# canSlaveV05.net
KiCad netlist of a schematic drawn in EAGLE
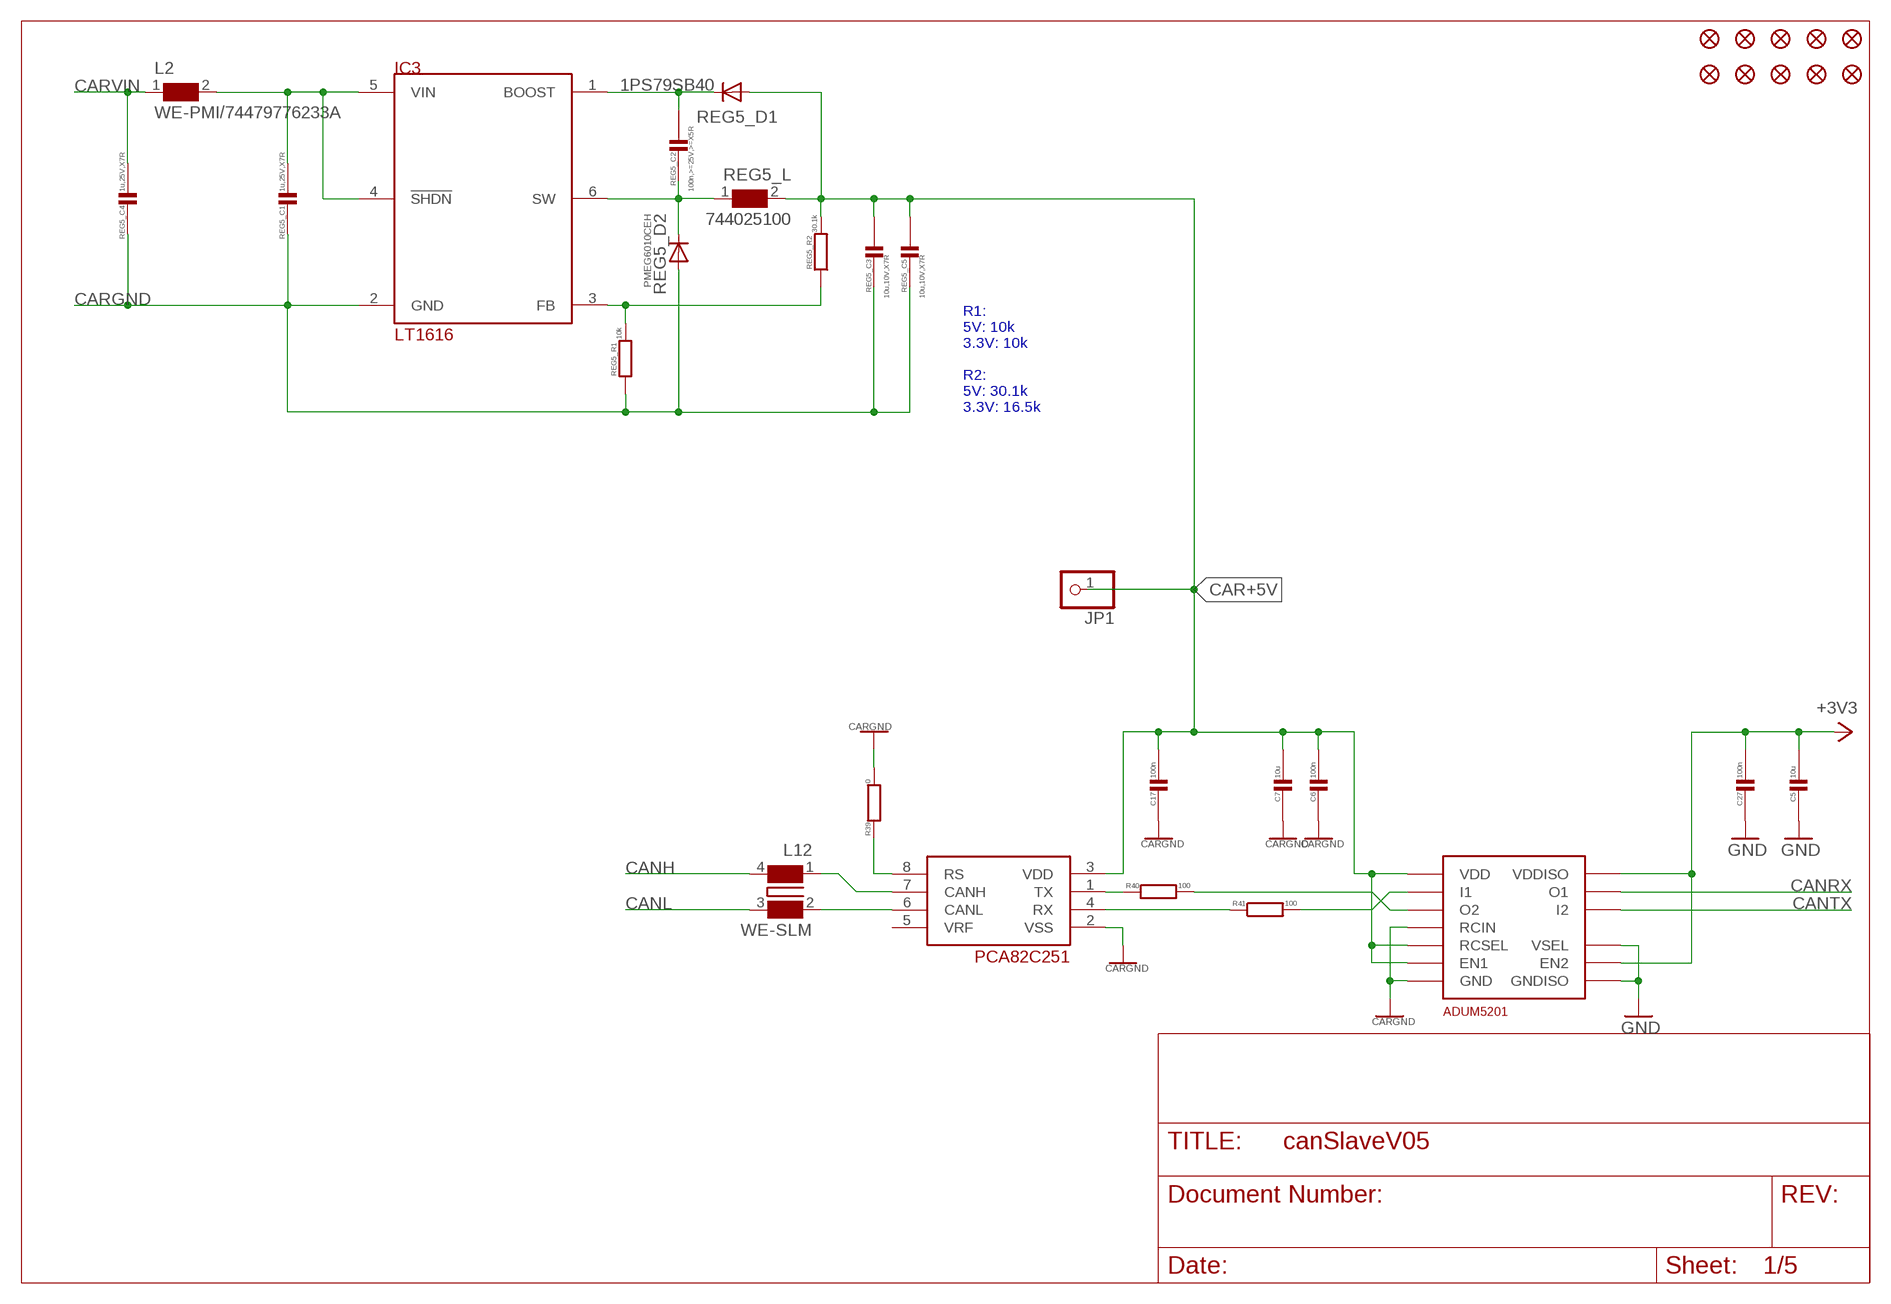
[diagram p0: schematic, sheet 1]
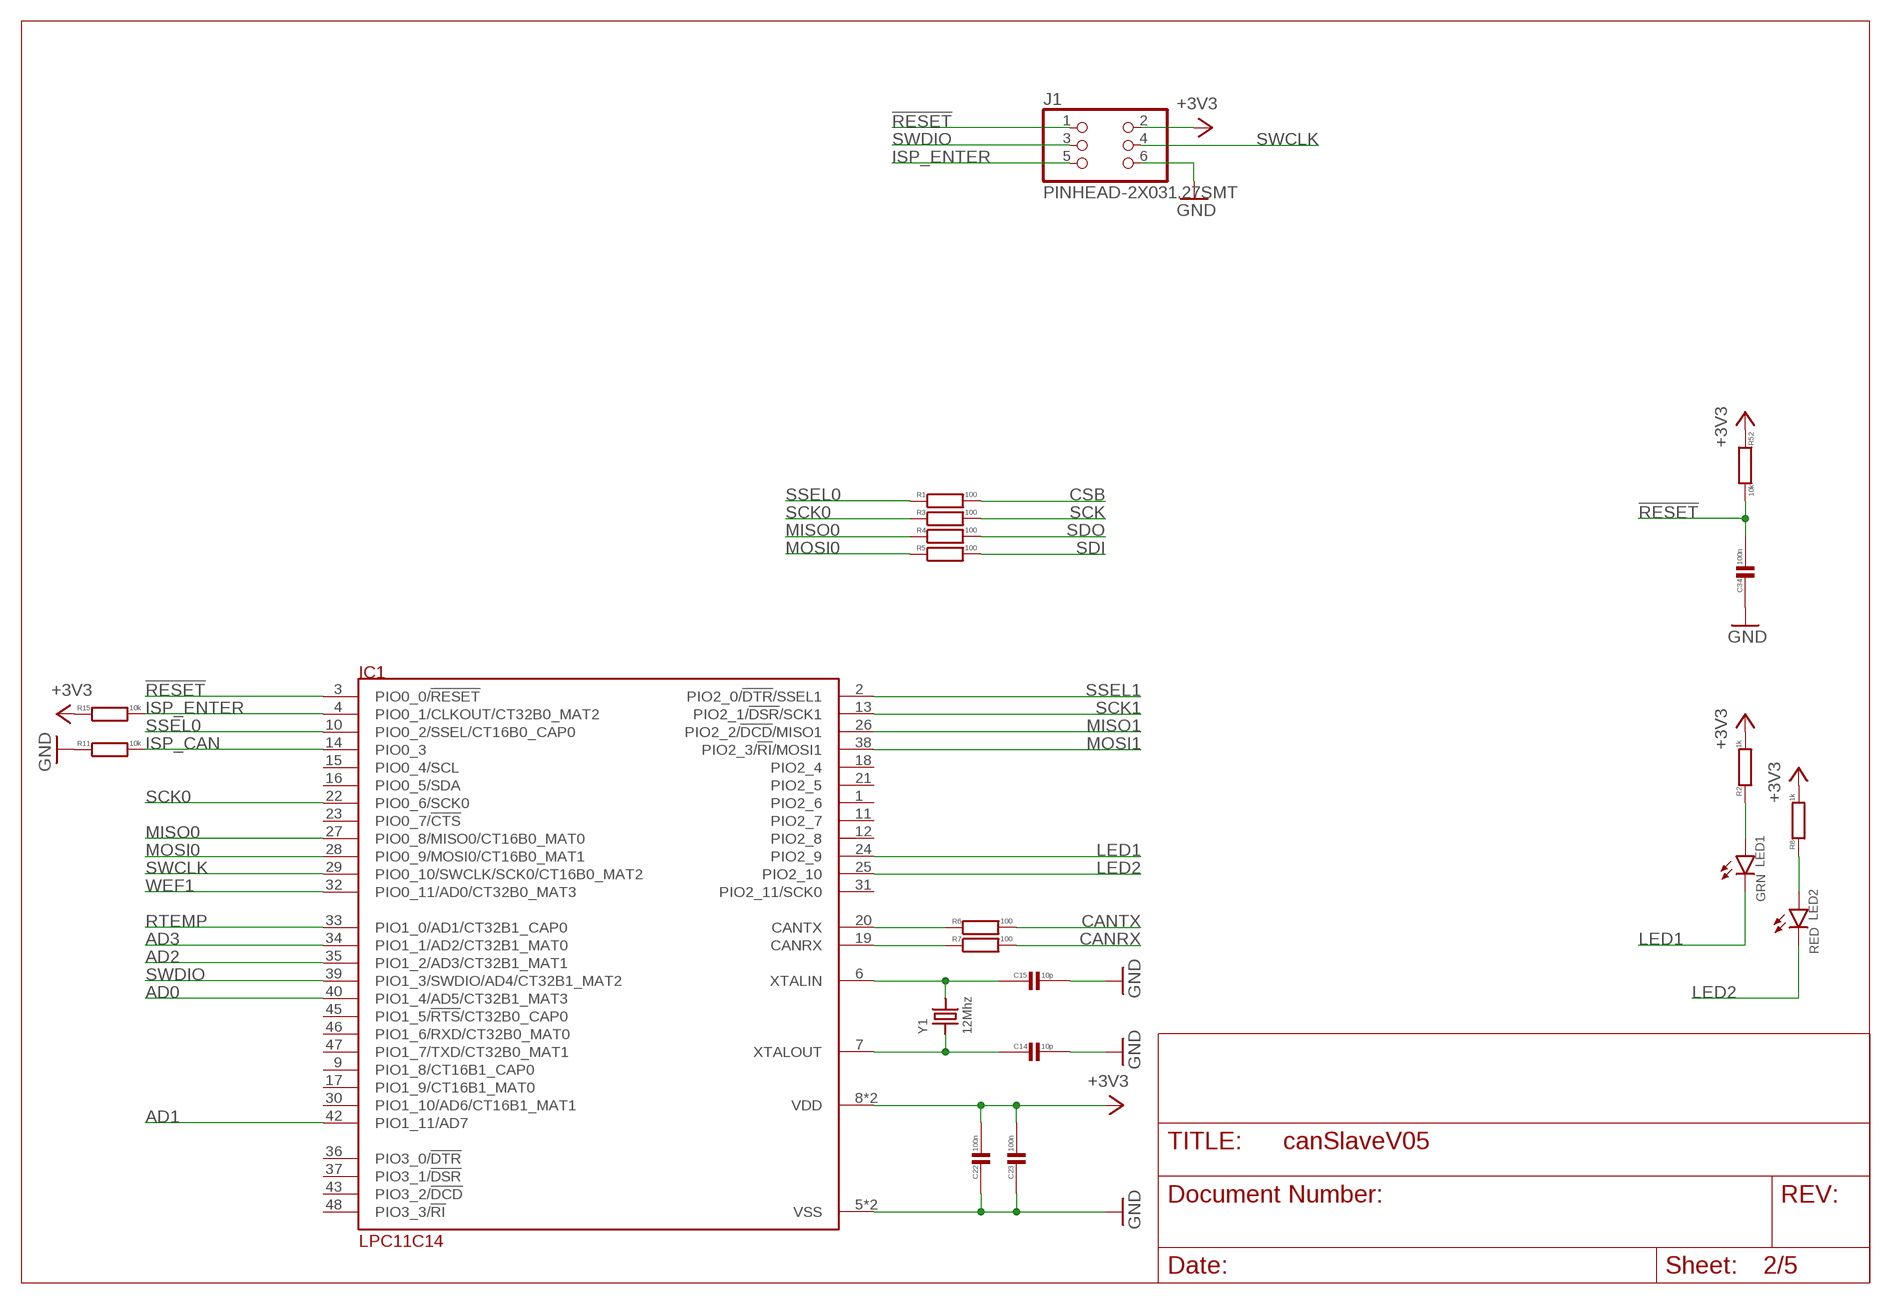
[diagram p1: schematic, sheet 2]
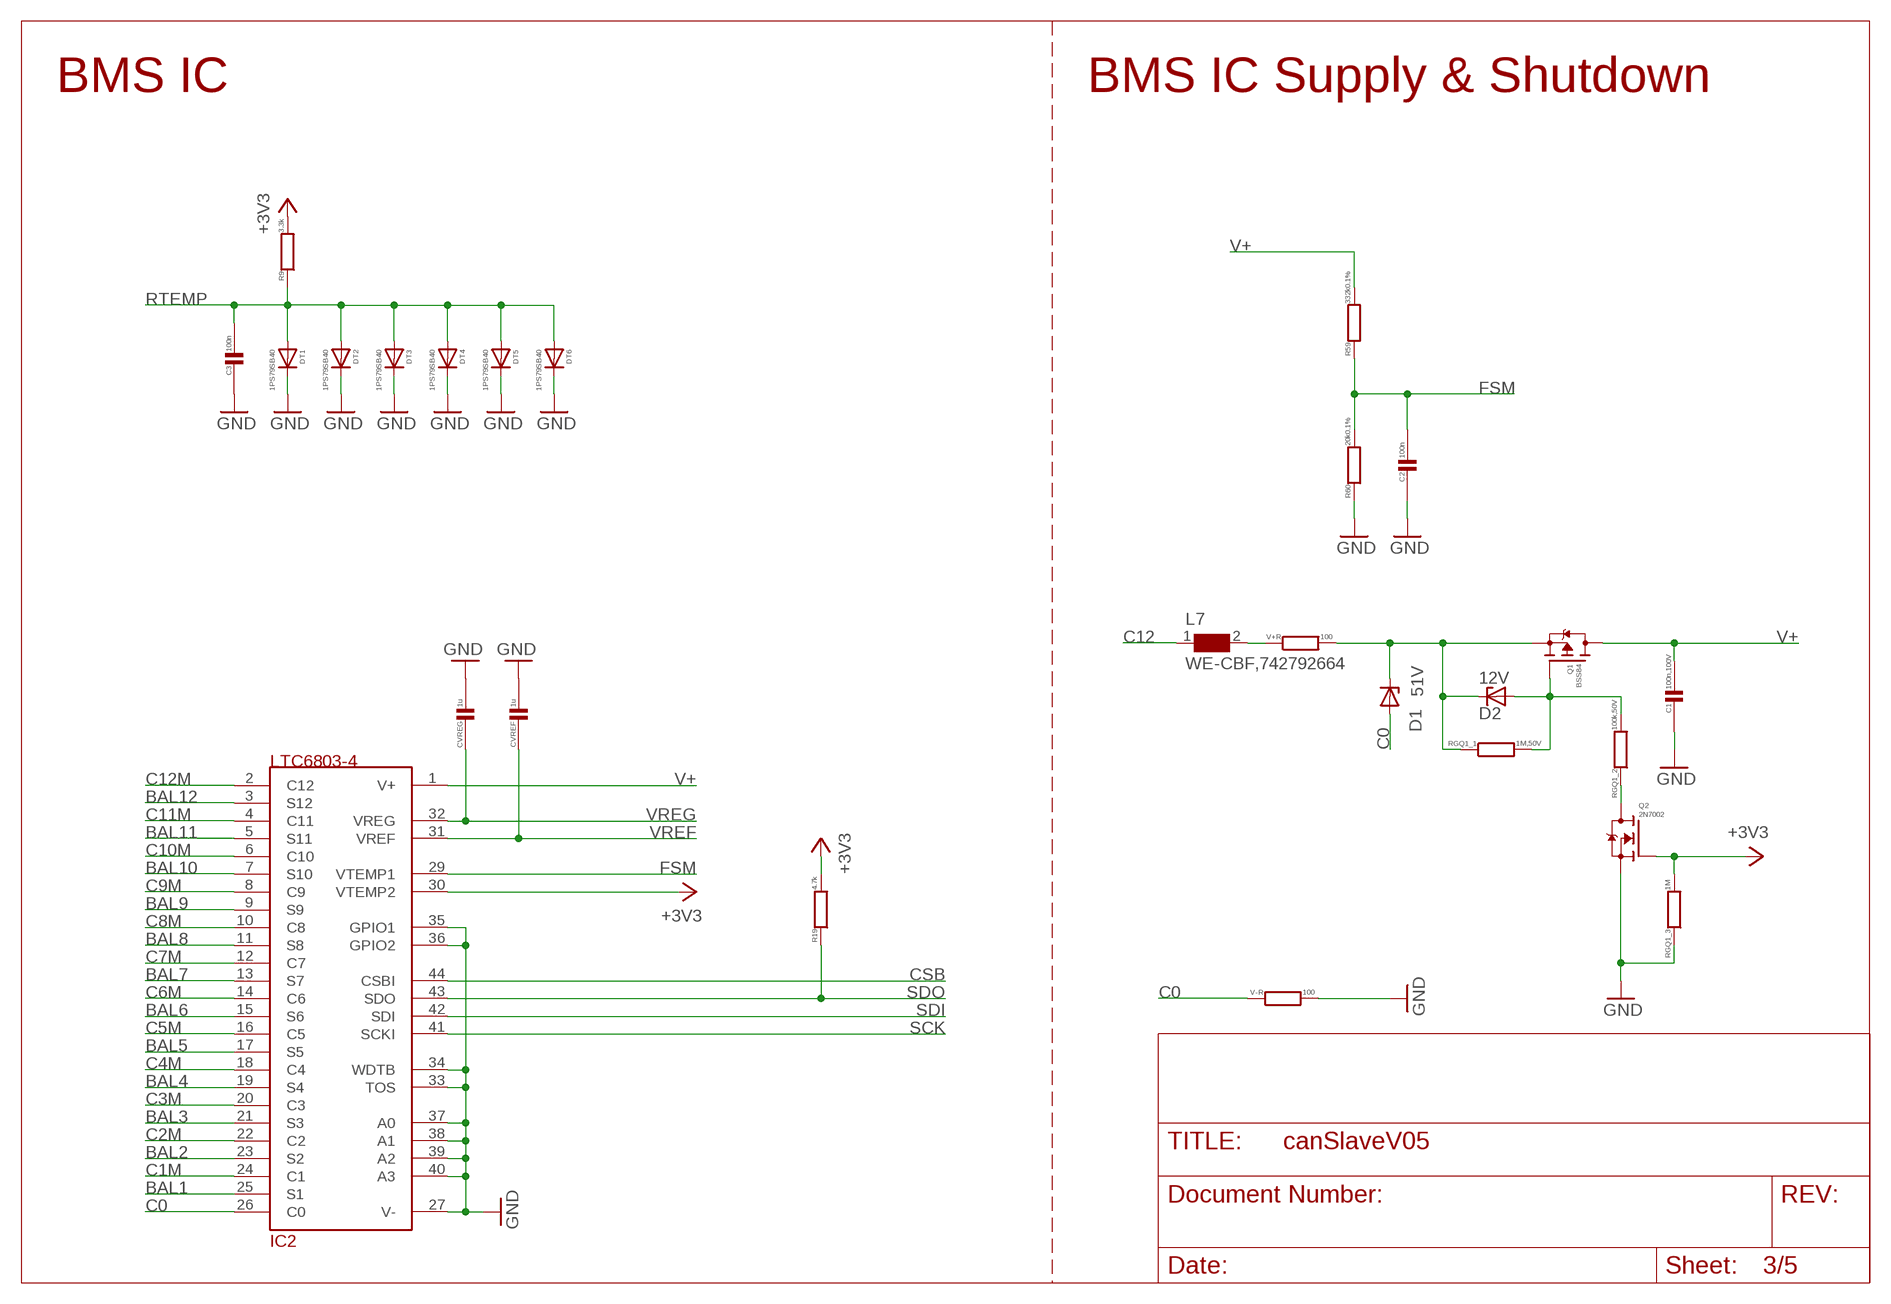
[diagram p2: schematic, sheet 3]
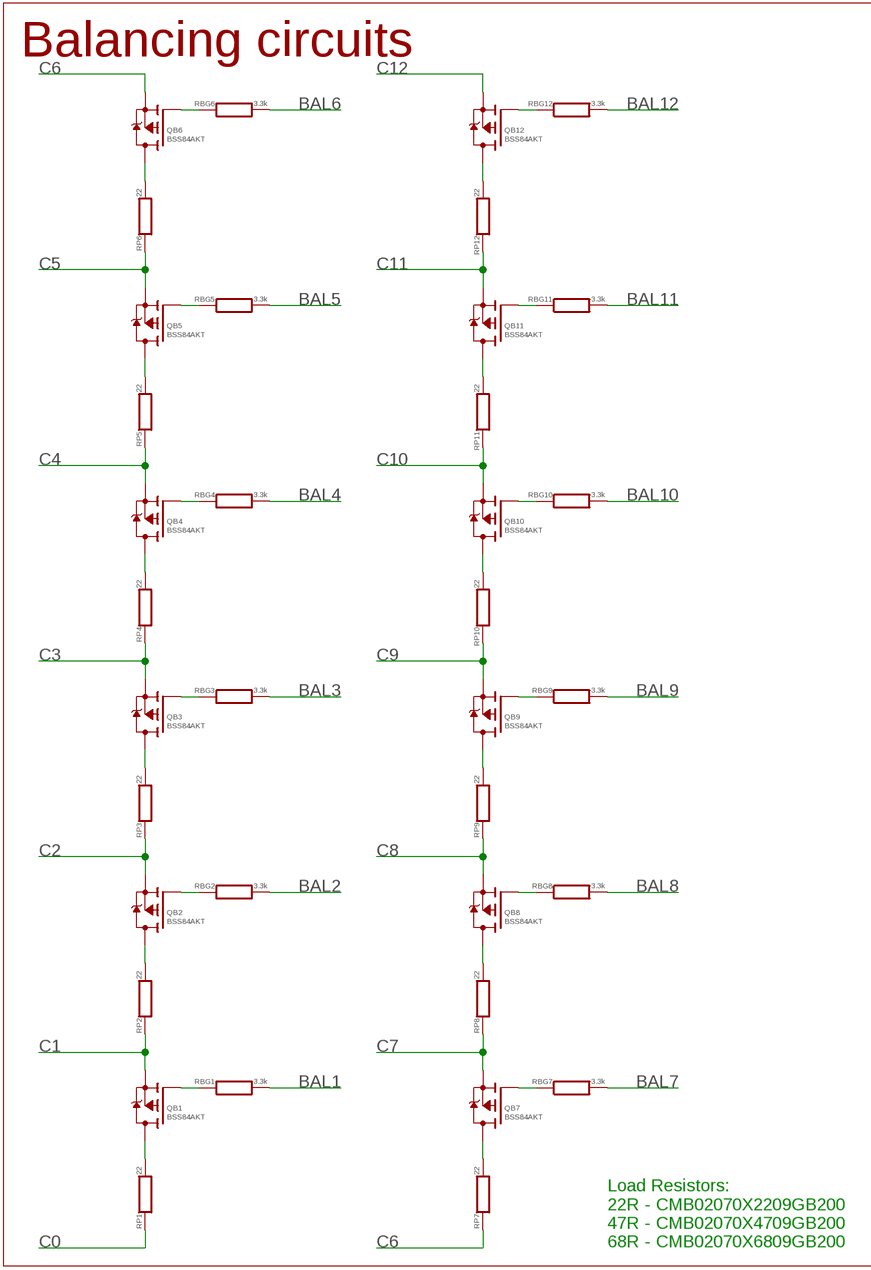
[diagram p3: schematic, sheet 4, part 1 of 2]
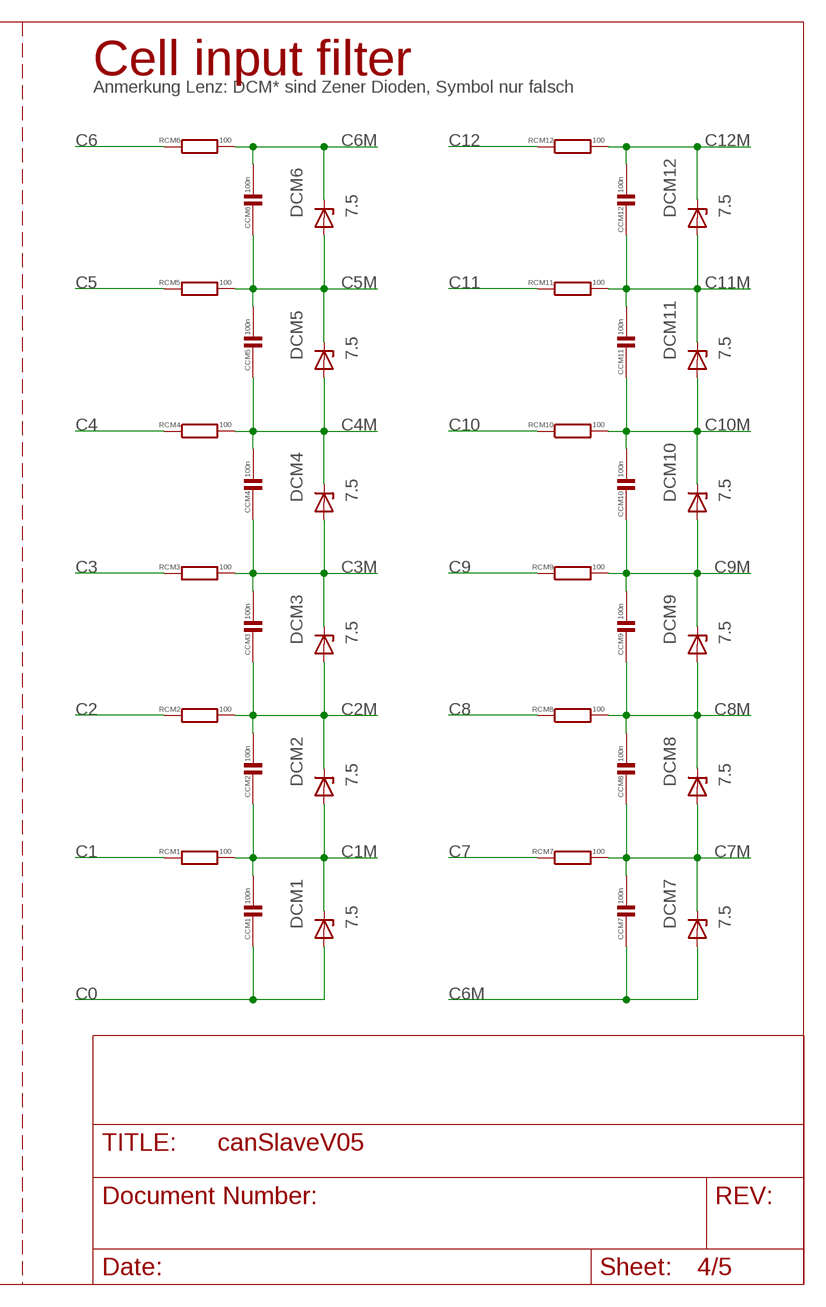
[diagram p4: schematic, sheet 4, part 2 of 2]
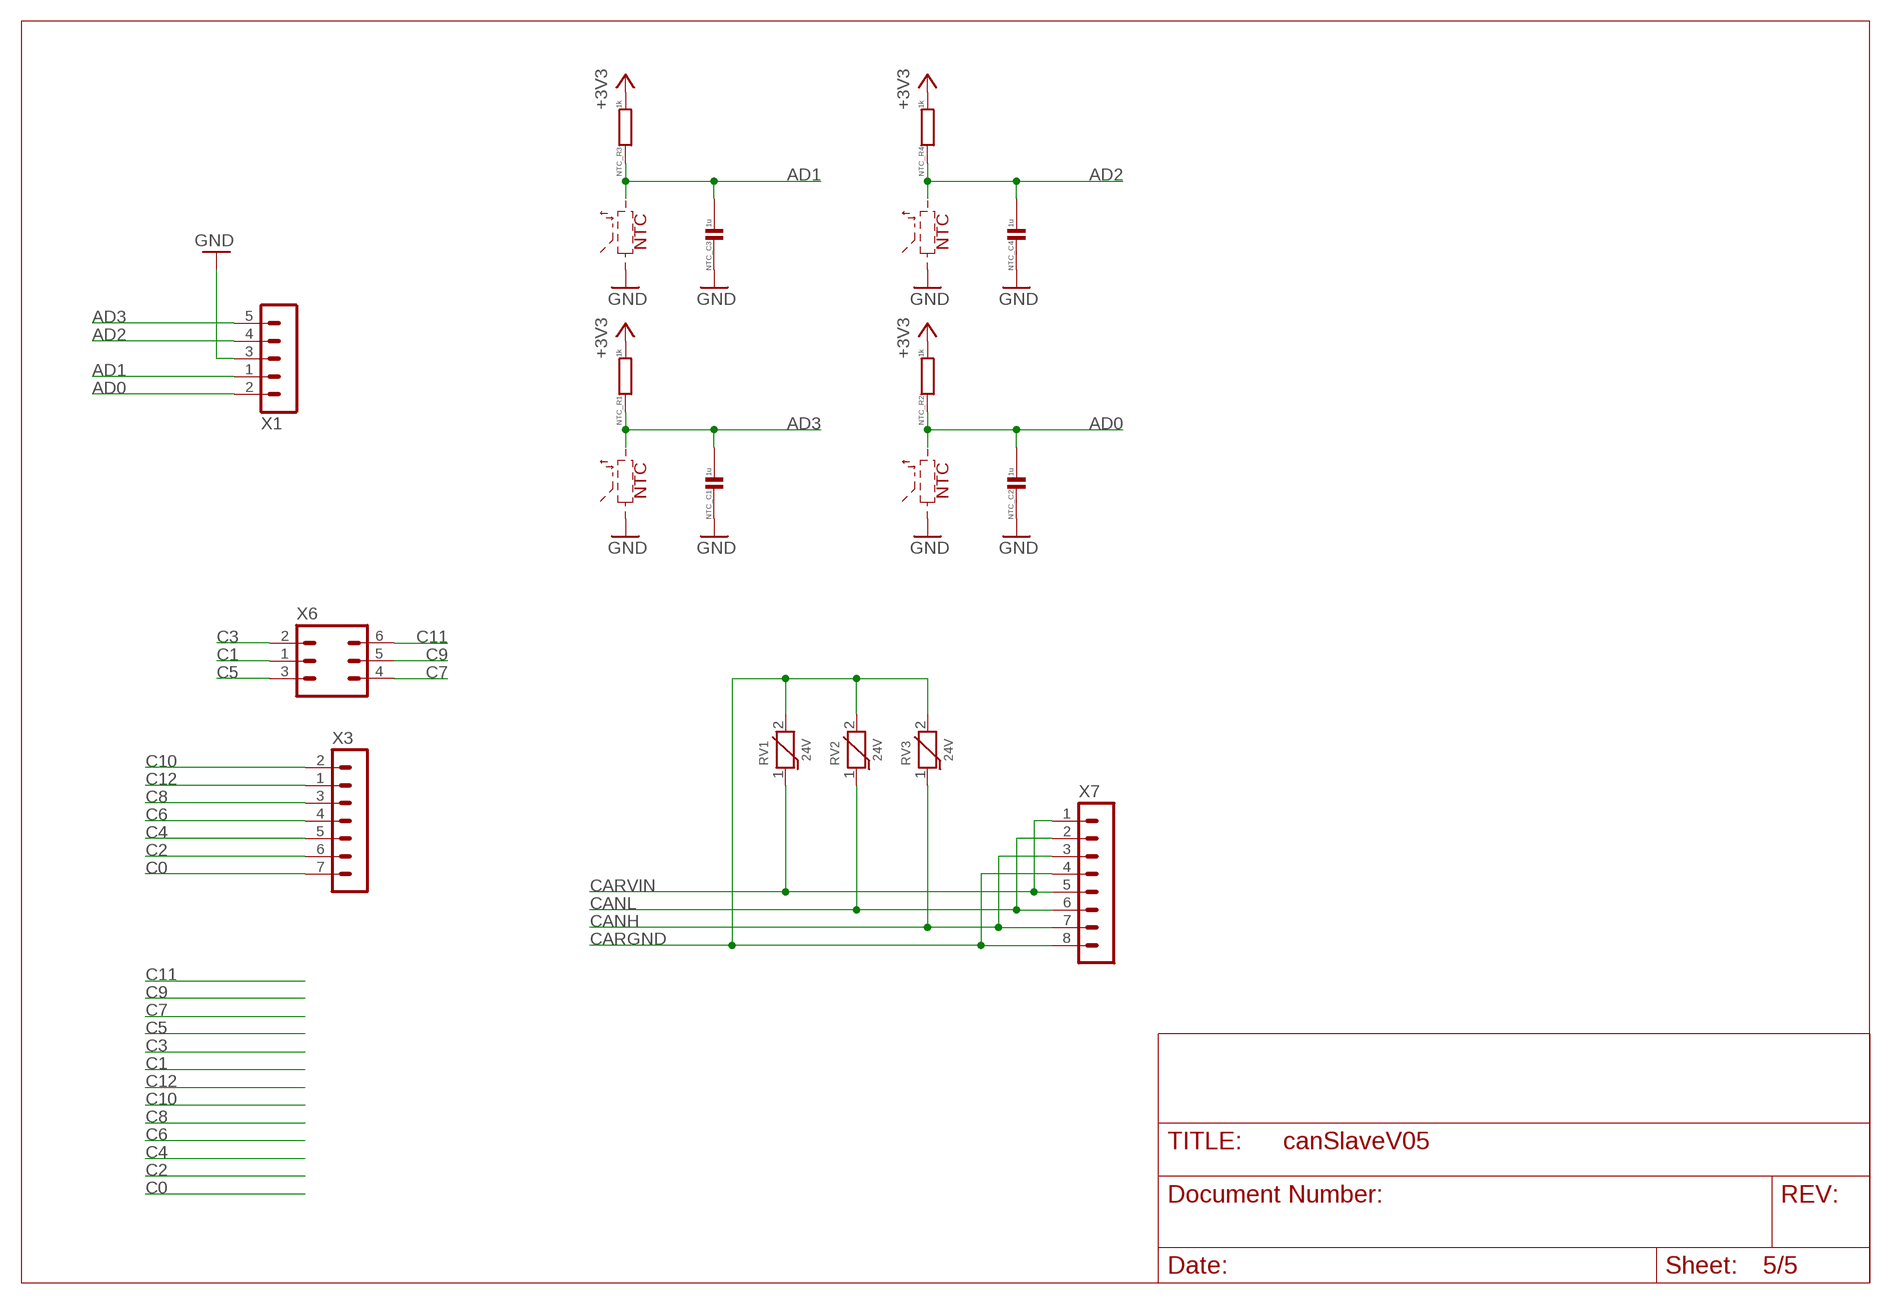
[diagram p5: schematic, sheet 5]

(export (version "E")
  (design (tool "Eeschema 10.0.6"))
  (components
    (comp (ref "CCM1")
      (value "100n")
      (footprint "eagle-import:C0402")
      (libsource (lib "eagle-import") (part "C0402"))
    )
    (comp (ref "CCM2")
      (value "100n")
      (footprint "eagle-import:C0402")
      (libsource (lib "eagle-import") (part "C0402"))
    )
    (comp (ref "CCM3")
      (value "100n")
      (footprint "eagle-import:C0402")
      (libsource (lib "eagle-import") (part "C0402"))
    )
    (comp (ref "CCM4")
      (value "100n")
      (footprint "eagle-import:C0402")
      (libsource (lib "eagle-import") (part "C0402"))
    )
    (comp (ref "CCM5")
      (value "100n")
      (footprint "eagle-import:C0402")
      (libsource (lib "eagle-import") (part "C0402"))
    )
    (comp (ref "CCM6")
      (value "100n")
      (footprint "eagle-import:C0402")
      (libsource (lib "eagle-import") (part "C0402"))
    )
    (comp (ref "CCM7")
      (value "100n")
      (footprint "eagle-import:C0402")
      (libsource (lib "eagle-import") (part "C0402"))
    )
    (comp (ref "CCM8")
      (value "100n")
      (footprint "eagle-import:C0402")
      (libsource (lib "eagle-import") (part "C0402"))
    )
    (comp (ref "CCM9")
      (value "100n")
      (footprint "eagle-import:C0402")
      (libsource (lib "eagle-import") (part "C0402"))
    )
    (comp (ref "CCM10")
      (value "100n")
      (footprint "eagle-import:C0402")
      (libsource (lib "eagle-import") (part "C0402"))
    )
    (comp (ref "CCM11")
      (value "100n")
      (footprint "eagle-import:C0402")
      (libsource (lib "eagle-import") (part "C0402"))
    )
    (comp (ref "CCM12")
      (value "100n")
      (footprint "eagle-import:C0402")
      (libsource (lib "eagle-import") (part "C0402"))
    )
    (comp (ref "DCM1")
      (value "7.5")
      (footprint "eagle-import:SOD523")
      (libsource (lib "eagle-import") (part "ZENERSOD523"))
    )
    (comp (ref "DCM2")
      (value "7.5")
      (footprint "eagle-import:SOD523")
      (libsource (lib "eagle-import") (part "ZENERSOD523"))
    )
    (comp (ref "DCM3")
      (value "7.5")
      (footprint "eagle-import:SOD523")
      (libsource (lib "eagle-import") (part "ZENERSOD523"))
    )
    (comp (ref "DCM4")
      (value "7.5")
      (footprint "eagle-import:SOD523")
      (libsource (lib "eagle-import") (part "ZENERSOD523"))
    )
    (comp (ref "DCM5")
      (value "7.5")
      (footprint "eagle-import:SOD523")
      (libsource (lib "eagle-import") (part "ZENERSOD523"))
    )
    (comp (ref "DCM6")
      (value "7.5")
      (footprint "eagle-import:SOD523")
      (libsource (lib "eagle-import") (part "ZENERSOD523"))
    )
    (comp (ref "DCM7")
      (value "7.5")
      (footprint "eagle-import:SOD523")
      (libsource (lib "eagle-import") (part "ZENERSOD523"))
    )
    (comp (ref "DCM8")
      (value "7.5")
      (footprint "eagle-import:SOD523")
      (libsource (lib "eagle-import") (part "ZENERSOD523"))
    )
    (comp (ref "DCM9")
      (value "7.5")
      (footprint "eagle-import:SOD523")
      (libsource (lib "eagle-import") (part "ZENERSOD523"))
    )
    (comp (ref "DCM10")
      (value "7.5")
      (footprint "eagle-import:SOD523")
      (libsource (lib "eagle-import") (part "ZENERSOD523"))
    )
    (comp (ref "DCM11")
      (value "7.5")
      (footprint "eagle-import:SOD523")
      (libsource (lib "eagle-import") (part "ZENERSOD523"))
    )
    (comp (ref "DCM12")
      (value "7.5")
      (footprint "eagle-import:SOD523")
      (libsource (lib "eagle-import") (part "ZENERSOD523"))
    )
    (comp (ref "QB1")
      (value "BSS84AKT")
      (footprint "eagle-import:SOT416")
      (libsource (lib "eagle-import") (part "BSS84AKT"))
    )
    (comp (ref "QB2")
      (value "BSS84AKT")
      (footprint "eagle-import:SOT416")
      (libsource (lib "eagle-import") (part "BSS84AKT"))
    )
    (comp (ref "QB3")
      (value "BSS84AKT")
      (footprint "eagle-import:SOT416")
      (libsource (lib "eagle-import") (part "BSS84AKT"))
    )
    (comp (ref "QB4")
      (value "BSS84AKT")
      (footprint "eagle-import:SOT416")
      (libsource (lib "eagle-import") (part "BSS84AKT"))
    )
    (comp (ref "QB5")
      (value "BSS84AKT")
      (footprint "eagle-import:SOT416")
      (libsource (lib "eagle-import") (part "BSS84AKT"))
    )
    (comp (ref "QB6")
      (value "BSS84AKT")
      (footprint "eagle-import:SOT416")
      (libsource (lib "eagle-import") (part "BSS84AKT"))
    )
    (comp (ref "QB7")
      (value "BSS84AKT")
      (footprint "eagle-import:SOT416")
      (libsource (lib "eagle-import") (part "BSS84AKT"))
    )
    (comp (ref "QB8")
      (value "BSS84AKT")
      (footprint "eagle-import:SOT416")
      (libsource (lib "eagle-import") (part "BSS84AKT"))
    )
    (comp (ref "QB9")
      (value "BSS84AKT")
      (footprint "eagle-import:SOT416")
      (libsource (lib "eagle-import") (part "BSS84AKT"))
    )
    (comp (ref "QB10")
      (value "BSS84AKT")
      (footprint "eagle-import:SOT416")
      (libsource (lib "eagle-import") (part "BSS84AKT"))
    )
    (comp (ref "QB11")
      (value "BSS84AKT")
      (footprint "eagle-import:SOT416")
      (libsource (lib "eagle-import") (part "BSS84AKT"))
    )
    (comp (ref "QB12")
      (value "BSS84AKT")
      (footprint "eagle-import:SOT416")
      (libsource (lib "eagle-import") (part "BSS84AKT"))
    )
    (comp (ref "RBG1")
      (value "3.3k")
      (footprint "eagle-import:R0402")
      (libsource (lib "eagle-import") (part "R0402"))
    )
    (comp (ref "RBG2")
      (value "3.3k")
      (footprint "eagle-import:R0402")
      (libsource (lib "eagle-import") (part "R0402"))
    )
    (comp (ref "RBG3")
      (value "3.3k")
      (footprint "eagle-import:R0402")
      (libsource (lib "eagle-import") (part "R0402"))
    )
    (comp (ref "RBG4")
      (value "3.3k")
      (footprint "eagle-import:R0402")
      (libsource (lib "eagle-import") (part "R0402"))
    )
    (comp (ref "RBG5")
      (value "3.3k")
      (footprint "eagle-import:R0402")
      (libsource (lib "eagle-import") (part "R0402"))
    )
    (comp (ref "RBG6")
      (value "3.3k")
      (footprint "eagle-import:R0402")
      (libsource (lib "eagle-import") (part "R0402"))
    )
    (comp (ref "RBG7")
      (value "3.3k")
      (footprint "eagle-import:R0402")
      (libsource (lib "eagle-import") (part "R0402"))
    )
    (comp (ref "RBG8")
      (value "3.3k")
      (footprint "eagle-import:R0402")
      (libsource (lib "eagle-import") (part "R0402"))
    )
    (comp (ref "RBG9")
      (value "3.3k")
      (footprint "eagle-import:R0402")
      (libsource (lib "eagle-import") (part "R0402"))
    )
    (comp (ref "RBG10")
      (value "3.3k")
      (footprint "eagle-import:R0402")
      (libsource (lib "eagle-import") (part "R0402"))
    )
    (comp (ref "RBG11")
      (value "3.3k")
      (footprint "eagle-import:R0402")
      (libsource (lib "eagle-import") (part "R0402"))
    )
    (comp (ref "RBG12")
      (value "3.3k")
      (footprint "eagle-import:R0402")
      (libsource (lib "eagle-import") (part "R0402"))
    )
    (comp (ref "RCM1")
      (value "100")
      (footprint "eagle-import:R0402")
      (libsource (lib "eagle-import") (part "R0402"))
    )
    (comp (ref "RCM2")
      (value "100")
      (footprint "eagle-import:R0402")
      (libsource (lib "eagle-import") (part "R0402"))
    )
    (comp (ref "RCM3")
      (value "100")
      (footprint "eagle-import:R0402")
      (libsource (lib "eagle-import") (part "R0402"))
    )
    (comp (ref "RCM4")
      (value "100")
      (footprint "eagle-import:R0402")
      (libsource (lib "eagle-import") (part "R0402"))
    )
    (comp (ref "RCM5")
      (value "100")
      (footprint "eagle-import:R0402")
      (libsource (lib "eagle-import") (part "R0402"))
    )
    (comp (ref "RCM6")
      (value "100")
      (footprint "eagle-import:R0402")
      (libsource (lib "eagle-import") (part "R0402"))
    )
    (comp (ref "RCM7")
      (value "100")
      (footprint "eagle-import:R0402")
      (libsource (lib "eagle-import") (part "R0402"))
    )
    (comp (ref "RCM8")
      (value "100")
      (footprint "eagle-import:R0402")
      (libsource (lib "eagle-import") (part "R0402"))
    )
    (comp (ref "RCM9")
      (value "100")
      (footprint "eagle-import:R0402")
      (libsource (lib "eagle-import") (part "R0402"))
    )
    (comp (ref "RCM10")
      (value "100")
      (footprint "eagle-import:R0402")
      (libsource (lib "eagle-import") (part "R0402"))
    )
    (comp (ref "RCM11")
      (value "100")
      (footprint "eagle-import:R0402")
      (libsource (lib "eagle-import") (part "R0402"))
    )
    (comp (ref "RCM12")
      (value "100")
      (footprint "eagle-import:R0402")
      (libsource (lib "eagle-import") (part "R0402"))
    )
    (comp (ref "RP1")
      (value "22")
      (footprint "eagle-import:MINI_MELF-0207R")
      (libsource (lib "eagle-import") (part "RMELF-0207R"))
    )
    (comp (ref "RP2")
      (value "22")
      (footprint "eagle-import:MINI_MELF-0207R")
      (libsource (lib "eagle-import") (part "RMELF-0207R"))
    )
    (comp (ref "RP3")
      (value "22")
      (footprint "eagle-import:MINI_MELF-0207R")
      (libsource (lib "eagle-import") (part "RMELF-0207R"))
    )
    (comp (ref "RP4")
      (value "22")
      (footprint "eagle-import:MINI_MELF-0207R")
      (libsource (lib "eagle-import") (part "RMELF-0207R"))
    )
    (comp (ref "RP5")
      (value "22")
      (footprint "eagle-import:MINI_MELF-0207R")
      (libsource (lib "eagle-import") (part "RMELF-0207R"))
    )
    (comp (ref "RP6")
      (value "22")
      (footprint "eagle-import:MINI_MELF-0207R")
      (libsource (lib "eagle-import") (part "RMELF-0207R"))
    )
    (comp (ref "RP7")
      (value "22")
      (footprint "eagle-import:MINI_MELF-0207R")
      (libsource (lib "eagle-import") (part "RMELF-0207R"))
    )
    (comp (ref "RP8")
      (value "22")
      (footprint "eagle-import:MINI_MELF-0207R")
      (libsource (lib "eagle-import") (part "RMELF-0207R"))
    )
    (comp (ref "RP9")
      (value "22")
      (footprint "eagle-import:MINI_MELF-0207R")
      (libsource (lib "eagle-import") (part "RMELF-0207R"))
    )
    (comp (ref "RP10")
      (value "22")
      (footprint "eagle-import:MINI_MELF-0207R")
      (libsource (lib "eagle-import") (part "RMELF-0207R"))
    )
    (comp (ref "RP11")
      (value "22")
      (footprint "eagle-import:MINI_MELF-0207R")
      (libsource (lib "eagle-import") (part "RMELF-0207R"))
    )
    (comp (ref "RP12")
      (value "22")
      (footprint "eagle-import:MINI_MELF-0207R")
      (libsource (lib "eagle-import") (part "RMELF-0207R"))
    )
    (comp (ref "C1")
      (value "100n,100V")
      (footprint "eagle-import:C0603")
      (libsource (lib "eagle-import") (part "C0603"))
    )
    (comp (ref "C2")
      (value "100n")
      (footprint "eagle-import:C0402")
      (libsource (lib "eagle-import") (part "C0402"))
    )
    (comp (ref "C3")
      (value "100n")
      (footprint "eagle-import:C0402")
      (libsource (lib "eagle-import") (part "C0402"))
    )
    (comp (ref "CVREF")
      (value "1u")
      (footprint "eagle-import:C0402")
      (libsource (lib "eagle-import") (part "C0402"))
    )
    (comp (ref "CVREG")
      (value "1u")
      (footprint "eagle-import:C0402")
      (libsource (lib "eagle-import") (part "C0402"))
    )
    (comp (ref "D1")
      (value "51V")
      (footprint "eagle-import:SOD323-L")
      (libsource (lib "eagle-import") (part "ZENERSOD323"))
    )
    (comp (ref "D2")
      (value "12V")
      (footprint "eagle-import:SOD323-L")
      (libsource (lib "eagle-import") (part "ZENERSOD323"))
    )
    (comp (ref "DT1")
      (value "1PS79SB40")
      (footprint "eagle-import:SOD523")
      (libsource (lib "eagle-import") (part "DIODE-SOD523"))
    )
    (comp (ref "DT2")
      (value "1PS79SB40")
      (footprint "eagle-import:SOD523")
      (libsource (lib "eagle-import") (part "DIODE-SOD523"))
    )
    (comp (ref "DT3")
      (value "1PS79SB40")
      (footprint "eagle-import:SOD523")
      (libsource (lib "eagle-import") (part "DIODE-SOD523"))
    )
    (comp (ref "DT4")
      (value "1PS79SB40")
      (footprint "eagle-import:SOD523")
      (libsource (lib "eagle-import") (part "DIODE-SOD523"))
    )
    (comp (ref "DT5")
      (value "1PS79SB40")
      (footprint "eagle-import:SOD523")
      (libsource (lib "eagle-import") (part "DIODE-SOD523"))
    )
    (comp (ref "DT6")
      (value "1PS79SB40")
      (footprint "eagle-import:SOD523")
      (libsource (lib "eagle-import") (part "DIODE-SOD523"))
    )
    (comp (ref "IC2")
      (value "LTC6803-4")
      (footprint "eagle-import:44SSOP")
      (libsource (lib "eagle-import") (part "LTC6803-4"))
    )
    (comp (ref "L7")
      (value "WE-CBF,742792664")
      (footprint "eagle-import:0603")
      (libsource (lib "eagle-import") (part "WE-CBF_0603"))
    )
    (comp (ref "Q1")
      (value "BSS84")
      (footprint "eagle-import:SOT23")
      (libsource (lib "eagle-import") (part "BSS84"))
    )
    (comp (ref "Q2")
      (value "2N7002")
      (footprint "eagle-import:SOT23")
      (libsource (lib "eagle-import") (part "2N7002"))
    )
    (comp (ref "R9")
      (value "3.3k")
      (footprint "eagle-import:R0603")
      (libsource (lib "eagle-import") (part "R0603"))
    )
    (comp (ref "R19")
      (value "4.7k")
      (footprint "eagle-import:R0402")
      (libsource (lib "eagle-import") (part "R0402"))
    )
    (comp (ref "R59")
      (value "332k0.1%")
      (footprint "eagle-import:R0603")
      (libsource (lib "eagle-import") (part "R0603"))
    )
    (comp (ref "R60")
      (value "20k0.1%")
      (footprint "eagle-import:R0402")
      (libsource (lib "eagle-import") (part "R0402"))
    )
    (comp (ref "RGQ1_1")
      (value "1M,50V")
      (footprint "eagle-import:R0603")
      (libsource (lib "eagle-import") (part "R0603"))
    )
    (comp (ref "RGQ1_2")
      (value "100k,50V")
      (footprint "eagle-import:R0603")
      (libsource (lib "eagle-import") (part "R0603"))
    )
    (comp (ref "RGQ1_3")
      (value "1M")
      (footprint "eagle-import:R0402")
      (libsource (lib "eagle-import") (part "R0402"))
    )
    (comp (ref "V+R")
      (value "100")
      (footprint "eagle-import:R0603")
      (libsource (lib "eagle-import") (part "R0603"))
    )
    (comp (ref "V-R")
      (value "100")
      (footprint "eagle-import:R0603")
      (libsource (lib "eagle-import") (part "R0603"))
    )
    (comp (ref "C14")
      (value "10p")
      (footprint "eagle-import:C0402")
      (libsource (lib "eagle-import") (part "C0402"))
    )
    (comp (ref "C15")
      (value "10p")
      (footprint "eagle-import:C0402")
      (libsource (lib "eagle-import") (part "C0402"))
    )
    (comp (ref "C22")
      (value "100n")
      (footprint "eagle-import:C0402")
      (libsource (lib "eagle-import") (part "C0402"))
    )
    (comp (ref "C23")
      (value "100n")
      (footprint "eagle-import:C0402")
      (libsource (lib "eagle-import") (part "C0402"))
    )
    (comp (ref "C34")
      (value "100n")
      (footprint "eagle-import:C0402")
      (libsource (lib "eagle-import") (part "C0402"))
    )
    (comp (ref "IC1")
      (value "LPC11C14")
      (footprint "eagle-import:LQFP48")
      (libsource (lib "eagle-import") (part "LPC11C1X"))
    )
    (comp (ref "J1")
      (value "PINHEAD-2X031.27SMT")
      (footprint "eagle-import:2X03_1.27MM_SMT")
      (libsource (lib "eagle-import") (part "PINHEAD-2X031.27SMT"))
    )
    (comp (ref "LED1")
      (value "GRN")
      (footprint "eagle-import:CHIPLED_0402")
      (libsource (lib "eagle-import") (part "LED0402"))
    )
    (comp (ref "LED2")
      (value "RED")
      (footprint "eagle-import:CHIPLED_0402")
      (libsource (lib "eagle-import") (part "LED0402"))
    )
    (comp (ref "R1")
      (value "100")
      (footprint "eagle-import:R0402")
      (libsource (lib "eagle-import") (part "R0402"))
    )
    (comp (ref "R2")
      (value "1k")
      (footprint "eagle-import:R0402")
      (libsource (lib "eagle-import") (part "R0402"))
    )
    (comp (ref "R3")
      (value "100")
      (footprint "eagle-import:R0402")
      (libsource (lib "eagle-import") (part "R0402"))
    )
    (comp (ref "R4")
      (value "100")
      (footprint "eagle-import:R0402")
      (libsource (lib "eagle-import") (part "R0402"))
    )
    (comp (ref "R5")
      (value "100")
      (footprint "eagle-import:R0402")
      (libsource (lib "eagle-import") (part "R0402"))
    )
    (comp (ref "R6")
      (value "100")
      (footprint "eagle-import:R0402")
      (libsource (lib "eagle-import") (part "R0402"))
    )
    (comp (ref "R7")
      (value "100")
      (footprint "eagle-import:R0402")
      (libsource (lib "eagle-import") (part "R0402"))
    )
    (comp (ref "R8")
      (value "1k")
      (footprint "eagle-import:R0402")
      (libsource (lib "eagle-import") (part "R0402"))
    )
    (comp (ref "R11")
      (value "10k")
      (footprint "eagle-import:R0402")
      (libsource (lib "eagle-import") (part "R0402"))
    )
    (comp (ref "R15")
      (value "10k")
      (footprint "eagle-import:R0402")
      (libsource (lib "eagle-import") (part "R0402"))
    )
    (comp (ref "R52")
      (value "10k")
      (footprint "eagle-import:R0402")
      (libsource (lib "eagle-import") (part "R0402"))
    )
    (comp (ref "Y1")
      (value "12Mhz")
      (footprint "eagle-import:CRYSTAL_3.2X2.5")
      (libsource (lib "eagle-import") (part "CRYSTALTHIN"))
    )
    (comp (ref "NTC_C1")
      (value "1u")
      (footprint "eagle-import:C0402")
      (libsource (lib "eagle-import") (part "C0402"))
    )
    (comp (ref "NTC_C2")
      (value "1u")
      (footprint "eagle-import:C0402")
      (libsource (lib "eagle-import") (part "C0402"))
    )
    (comp (ref "NTC_C3")
      (value "1u")
      (footprint "eagle-import:C0402")
      (libsource (lib "eagle-import") (part "C0402"))
    )
    (comp (ref "NTC_C4")
      (value "1u")
      (footprint "eagle-import:C0402")
      (libsource (lib "eagle-import") (part "C0402"))
    )
    (comp (ref "NTC_R1")
      (value "1k")
      (footprint "eagle-import:R0402")
      (libsource (lib "eagle-import") (part "R0402"))
    )
    (comp (ref "NTC_R2")
      (value "1k")
      (footprint "eagle-import:R0402")
      (libsource (lib "eagle-import") (part "R0402"))
    )
    (comp (ref "NTC_R3")
      (value "1k")
      (footprint "eagle-import:R0402")
      (libsource (lib "eagle-import") (part "R0402"))
    )
    (comp (ref "NTC_R4")
      (value "1k")
      (footprint "eagle-import:R0402")
      (libsource (lib "eagle-import") (part "R0402"))
    )
    (comp (ref "RV1")
      (value "24V")
      (footprint "eagle-import:R0805")
      (libsource (lib "eagle-import") (part "VARISTOR0805"))
    )
    (comp (ref "RV2")
      (value "24V")
      (footprint "eagle-import:R0603")
      (libsource (lib "eagle-import") (part "VARISTOR0603"))
    )
    (comp (ref "RV3")
      (value "24V")
      (footprint "eagle-import:R0603")
      (libsource (lib "eagle-import") (part "VARISTOR0603"))
    )
    (comp (ref "X1")
      (value "HEADER_POS5_43650-0509")
      (footprint "eagle-import:43650-0509")
      (libsource (lib "eagle-import") (part "HEADER_POS5_?43650-0509"))
    )
    (comp (ref "X3")
      (value "HEADER_POS7_43650-0709")
      (footprint "eagle-import:43650-0709")
      (libsource (lib "eagle-import") (part "HEADER_POS7_?43650-0709"))
    )
    (comp (ref "X6")
      (value "HEADER_POS6_43650-0609")
      (footprint "eagle-import:43650-0609")
      (libsource (lib "eagle-import") (part "HEADER_POS6_?43650-0609"))
    )
    (comp (ref "X7")
      (value "HEADER_POS8_43045-0800")
      (footprint "eagle-import:43045-0800")
      (libsource (lib "eagle-import") (part "HEADER_POS8_?43045-0800"))
    )
    (comp (ref "C5")
      (value "10u")
      (footprint "eagle-import:C0603")
      (libsource (lib "eagle-import") (part "C0603"))
    )
    (comp (ref "C6")
      (value "100n")
      (footprint "eagle-import:C0402")
      (libsource (lib "eagle-import") (part "C0402"))
    )
    (comp (ref "C7")
      (value "10u")
      (footprint "eagle-import:C0603")
      (libsource (lib "eagle-import") (part "C0603"))
    )
    (comp (ref "C17")
      (value "100n")
      (footprint "eagle-import:C0402")
      (libsource (lib "eagle-import") (part "C0402"))
    )
    (comp (ref "C27")
      (value "100n")
      (footprint "eagle-import:C0402")
      (libsource (lib "eagle-import") (part "C0402"))
    )
    (comp (ref "FID1")
      (value "FIDUCIAL\"\"")
      (footprint "eagle-import:FIDUCIAL_1MM")
      (libsource (lib "eagle-import") (part "FIDUCIAL{dblquote}{dblquote}"))
    )
    (comp (ref "FID2")
      (value "FIDUCIAL\"\"")
      (footprint "eagle-import:FIDUCIAL_1MM")
      (libsource (lib "eagle-import") (part "FIDUCIAL{dblquote}{dblquote}"))
    )
    (comp (ref "FID3")
      (value "FIDUCIAL\"\"")
      (footprint "eagle-import:FIDUCIAL_1MM")
      (libsource (lib "eagle-import") (part "FIDUCIAL{dblquote}{dblquote}"))
    )
    (comp (ref "FID4")
      (value "FIDUCIAL\"\"")
      (footprint "eagle-import:FIDUCIAL_1MM")
      (libsource (lib "eagle-import") (part "FIDUCIAL{dblquote}{dblquote}"))
    )
    (comp (ref "FID5")
      (value "FIDUCIAL\"\"")
      (footprint "eagle-import:FIDUCIAL_1MM")
      (libsource (lib "eagle-import") (part "FIDUCIAL{dblquote}{dblquote}"))
    )
    (comp (ref "FID6")
      (value "FIDUCIAL\"\"")
      (footprint "eagle-import:FIDUCIAL_1MM")
      (libsource (lib "eagle-import") (part "FIDUCIAL{dblquote}{dblquote}"))
    )
    (comp (ref "FID7")
      (value "FIDUCIAL\"\"")
      (footprint "eagle-import:FIDUCIAL_1MM")
      (libsource (lib "eagle-import") (part "FIDUCIAL{dblquote}{dblquote}"))
    )
    (comp (ref "FID8")
      (value "FIDUCIAL\"\"")
      (footprint "eagle-import:FIDUCIAL_1MM")
      (libsource (lib "eagle-import") (part "FIDUCIAL{dblquote}{dblquote}"))
    )
    (comp (ref "FID9")
      (value "FIDUCIAL\"\"")
      (footprint "eagle-import:FIDUCIAL_1MM")
      (libsource (lib "eagle-import") (part "FIDUCIAL{dblquote}{dblquote}"))
    )
    (comp (ref "FID10")
      (value "FIDUCIAL\"\"")
      (footprint "eagle-import:FIDUCIAL_1MM")
      (libsource (lib "eagle-import") (part "FIDUCIAL{dblquote}{dblquote}"))
    )
    (comp (ref "IC3")
      (value "LT1616")
      (footprint "eagle-import:SOT23-6")
      (libsource (lib "eagle-import") (part "LT1616"))
    )
    (comp (ref "IC5")
      (value "PCA82C251")
      (footprint "eagle-import:SO-8")
      (libsource (lib "eagle-import") (part "MCP2551"))
    )
    (comp (ref "JP1")
      (value "PINHD-1X1")
      (footprint "eagle-import:1X01")
      (libsource (lib "eagle-import") (part "PINHD-1X1"))
    )
    (comp (ref "L2")
      (value "WE-PMI/74479776233A")
      (footprint "eagle-import:WE-PMI_0806")
      (libsource (lib "eagle-import") (part "WE-PMI_0806"))
    )
    (comp (ref "L12")
      (value "WE-SLM")
      (footprint "eagle-import:WE-SLM")
      (libsource (lib "eagle-import") (part "WE-SLM"))
    )
    (comp (ref "R39")
      (value "0")
      (footprint "eagle-import:R0402")
      (libsource (lib "eagle-import") (part "R0402"))
    )
    (comp (ref "R40")
      (value "100")
      (footprint "eagle-import:R0402")
      (libsource (lib "eagle-import") (part "R0402"))
    )
    (comp (ref "R41")
      (value "100")
      (footprint "eagle-import:R0402")
      (libsource (lib "eagle-import") (part "R0402"))
    )
    (comp (ref "REG5_C1")
      (value "1u,25V,X7R")
      (footprint "eagle-import:C0805")
      (libsource (lib "eagle-import") (part "C0805"))
    )
    (comp (ref "REG5_C2")
      (value "100n,>=25V,>=X5R")
      (footprint "eagle-import:C0402")
      (libsource (lib "eagle-import") (part "C0402"))
    )
    (comp (ref "REG5_C3")
      (value "10u,10V,X7R")
      (footprint "eagle-import:C0805")
      (libsource (lib "eagle-import") (part "C0805"))
    )
    (comp (ref "REG5_C4")
      (value "1u,25V,X7R")
      (footprint "eagle-import:C0805")
      (libsource (lib "eagle-import") (part "C0805"))
    )
    (comp (ref "REG5_C5")
      (value "10u,10V,X7R")
      (footprint "eagle-import:C0805")
      (libsource (lib "eagle-import") (part "C0805"))
    )
    (comp (ref "REG5_D1")
      (value "1PS79SB40")
      (footprint "eagle-import:SOD523")
      (libsource (lib "eagle-import") (part "DIODE-SOD523"))
    )
    (comp (ref "REG5_D2")
      (value "PMEG6010CEH")
      (footprint "eagle-import:SOD123")
      (libsource (lib "eagle-import") (part "D-SOD123"))
    )
    (comp (ref "REG5_L")
      (value "744025100")
      (footprint "eagle-import:WE-TPC_2828")
      (libsource (lib "eagle-import") (part "WE-TPC_2828"))
    )
    (comp (ref "REG5_R1")
      (value "10k")
      (footprint "eagle-import:R0402")
      (libsource (lib "eagle-import") (part "R0402"))
    )
    (comp (ref "REG5_R2")
      (value "30.1k")
      (footprint "eagle-import:R0402")
      (libsource (lib "eagle-import") (part "R0402"))
    )
    (comp (ref "U$2")
      (value "ADUM5201")
      (footprint "eagle-import:SO16WB")
      (libsource (lib "eagle-import") (part "ADUM5201"))
    )
  )
  (nets
    (net (code "1") (name "+3V3") (class "Default")
      (node (ref "C22") (pin "1") (pinfunction "1_1") (pintype "passive"))
      (node (ref "C23") (pin "1") (pinfunction "1_1") (pintype "passive"))
      (node (ref "C27") (pin "1") (pinfunction "1_1") (pintype "passive"))
      (node (ref "C5") (pin "1") (pinfunction "1_1") (pintype "passive"))
      (node (ref "IC1") (pin "44") (pinfunction "VDD_44") (pintype "bidirectional"))
      (node (ref "IC1") (pin "8") (pinfunction "VDD_8") (pintype "bidirectional"))
      (node (ref "IC2") (pin "30") (pinfunction "VTEMP2_30") (pintype "bidirectional"))
      (node (ref "J1") (pin "2") (pinfunction "2_2") (pintype "passive"))
      (node (ref "NTC_R1") (pin "2") (pinfunction "2_2") (pintype "passive"))
      (node (ref "NTC_R2") (pin "2") (pinfunction "2_2") (pintype "passive"))
      (node (ref "NTC_R3") (pin "2") (pinfunction "2_2") (pintype "passive"))
      (node (ref "NTC_R4") (pin "2") (pinfunction "2_2") (pintype "passive"))
      (node (ref "Q2") (pin "1") (pinfunction "G_1") (pintype "passive"))
      (node (ref "R15") (pin "1") (pinfunction "1_1") (pintype "passive"))
      (node (ref "R19") (pin "2") (pinfunction "2_2") (pintype "passive"))
      (node (ref "R2") (pin "2") (pinfunction "2_2") (pintype "passive"))
      (node (ref "R52") (pin "1") (pinfunction "1_1") (pintype "passive"))
      (node (ref "R8") (pin "2") (pinfunction "2_2") (pintype "passive"))
      (node (ref "R9") (pin "2") (pinfunction "2_2") (pintype "passive"))
      (node (ref "RGQ1_3") (pin "2") (pinfunction "2_2") (pintype "passive"))
      (node (ref "U$2") (pin "P$10") (pinfunction "EN2_P$10") (pintype "bidirectional"))
      (node (ref "U$2") (pin "P$16") (pinfunction "VDDISO_P$16") (pintype "bidirectional"))
    )
    (net (code "2") (name "AD0") (class "Default")
      (node (ref "IC1") (pin "40") (pinfunction "PIO1_4/AD5/CT32B1_MAT3_40") (pintype "bidirectional"))
      (node (ref "NTC_C2") (pin "1") (pinfunction "1_1") (pintype "passive"))
      (node (ref "NTC_R2") (pin "1") (pinfunction "1_1") (pintype "passive"))
      (node (ref "X1") (pin "2") (pinfunction "1_2") (pintype "passive"))
    )
    (net (code "3") (name "AD1") (class "Default")
      (node (ref "IC1") (pin "42") (pinfunction "PIO1_11/AD7_42") (pintype "bidirectional"))
      (node (ref "NTC_C3") (pin "1") (pinfunction "1_1") (pintype "passive"))
      (node (ref "NTC_R3") (pin "1") (pinfunction "1_1") (pintype "passive"))
      (node (ref "X1") (pin "1") (pinfunction "2_1") (pintype "passive"))
    )
    (net (code "4") (name "AD2") (class "Default")
      (node (ref "IC1") (pin "35") (pinfunction "PIO1_2/AD3/CT32B1_MAT1_35") (pintype "bidirectional"))
      (node (ref "NTC_C4") (pin "1") (pinfunction "1_1") (pintype "passive"))
      (node (ref "NTC_R4") (pin "1") (pinfunction "1_1") (pintype "passive"))
      (node (ref "X1") (pin "4") (pinfunction "4_4") (pintype "passive"))
    )
    (net (code "5") (name "AD3") (class "Default")
      (node (ref "IC1") (pin "34") (pinfunction "PIO1_1/AD2/CT32B1_MAT0_34") (pintype "bidirectional"))
      (node (ref "NTC_C1") (pin "1") (pinfunction "1_1") (pintype "passive"))
      (node (ref "NTC_R1") (pin "1") (pinfunction "1_1") (pintype "passive"))
      (node (ref "X1") (pin "5") (pinfunction "5_5") (pintype "passive"))
    )
    (net (code "6") (name "BAL1") (class "Default")
      (node (ref "IC2") (pin "25") (pinfunction "S1_25") (pintype "bidirectional"))
      (node (ref "RBG1") (pin "2") (pinfunction "2_2") (pintype "passive"))
    )
    (net (code "7") (name "BAL2") (class "Default")
      (node (ref "IC2") (pin "23") (pinfunction "S2_23") (pintype "bidirectional"))
      (node (ref "RBG2") (pin "2") (pinfunction "2_2") (pintype "passive"))
    )
    (net (code "8") (name "BAL3") (class "Default")
      (node (ref "IC2") (pin "21") (pinfunction "S3_21") (pintype "bidirectional"))
      (node (ref "RBG3") (pin "2") (pinfunction "2_2") (pintype "passive"))
    )
    (net (code "9") (name "BAL4") (class "Default")
      (node (ref "IC2") (pin "19") (pinfunction "S4_19") (pintype "bidirectional"))
      (node (ref "RBG4") (pin "2") (pinfunction "2_2") (pintype "passive"))
    )
    (net (code "10") (name "BAL5") (class "Default")
      (node (ref "IC2") (pin "17") (pinfunction "S5_17") (pintype "bidirectional"))
      (node (ref "RBG5") (pin "2") (pinfunction "2_2") (pintype "passive"))
    )
    (net (code "11") (name "BAL6") (class "Default")
      (node (ref "IC2") (pin "15") (pinfunction "S6_15") (pintype "bidirectional"))
      (node (ref "RBG6") (pin "2") (pinfunction "2_2") (pintype "passive"))
    )
    (net (code "12") (name "BAL7") (class "Default")
      (node (ref "IC2") (pin "13") (pinfunction "S7_13") (pintype "bidirectional"))
      (node (ref "RBG7") (pin "2") (pinfunction "2_2") (pintype "passive"))
    )
    (net (code "13") (name "BAL8") (class "Default")
      (node (ref "IC2") (pin "11") (pinfunction "S8_11") (pintype "bidirectional"))
      (node (ref "RBG8") (pin "2") (pinfunction "2_2") (pintype "passive"))
    )
    (net (code "14") (name "BAL9") (class "Default")
      (node (ref "IC2") (pin "9") (pinfunction "S9_9") (pintype "bidirectional"))
      (node (ref "RBG9") (pin "2") (pinfunction "2_2") (pintype "passive"))
    )
    (net (code "15") (name "BAL10") (class "Default")
      (node (ref "IC2") (pin "7") (pinfunction "S10_7") (pintype "bidirectional"))
      (node (ref "RBG10") (pin "2") (pinfunction "2_2") (pintype "passive"))
    )
    (net (code "16") (name "BAL11") (class "Default")
      (node (ref "IC2") (pin "5") (pinfunction "S11_5") (pintype "bidirectional"))
      (node (ref "RBG11") (pin "2") (pinfunction "2_2") (pintype "passive"))
    )
    (net (code "17") (name "BAL12") (class "Default")
      (node (ref "IC2") (pin "3") (pinfunction "S12_3") (pintype "bidirectional"))
      (node (ref "RBG12") (pin "2") (pinfunction "2_2") (pintype "passive"))
    )
    (net (code "18") (name "C0") (class "Default")
      (node (ref "CCM1") (pin "2") (pinfunction "2_2") (pintype "passive"))
      (node (ref "D1") (pin "A") (pinfunction "A_A") (pintype "passive"))
      (node (ref "DCM1") (pin "A") (pinfunction "A_A") (pintype "passive"))
      (node (ref "IC2") (pin "26") (pinfunction "C0_26") (pintype "bidirectional"))
      (node (ref "RP1") (pin "1") (pinfunction "1_1") (pintype "passive"))
      (node (ref "V-R") (pin "1") (pinfunction "1_1") (pintype "passive"))
      (node (ref "X3") (pin "7") (pinfunction "7_7") (pintype "passive"))
    )
    (net (code "19") (name "C1") (class "Default")
      (node (ref "QB1") (pin "2") (pinfunction "S_2") (pintype "passive"))
      (node (ref "RCM1") (pin "1") (pinfunction "1_1") (pintype "passive"))
      (node (ref "RP2") (pin "1") (pinfunction "1_1") (pintype "passive"))
      (node (ref "X6") (pin "1") (pinfunction "2_1") (pintype "passive"))
    )
    (net (code "20") (name "C1M") (class "Default")
      (node (ref "CCM1") (pin "1") (pinfunction "1_1") (pintype "passive"))
      (node (ref "CCM2") (pin "2") (pinfunction "2_2") (pintype "passive"))
      (node (ref "DCM1") (pin "C") (pinfunction "C_C") (pintype "passive"))
      (node (ref "DCM2") (pin "A") (pinfunction "A_A") (pintype "passive"))
      (node (ref "IC2") (pin "24") (pinfunction "C1_24") (pintype "bidirectional"))
      (node (ref "RCM1") (pin "2") (pinfunction "2_2") (pintype "passive"))
    )
    (net (code "21") (name "C2") (class "Default")
      (node (ref "QB2") (pin "2") (pinfunction "S_2") (pintype "passive"))
      (node (ref "RCM2") (pin "1") (pinfunction "1_1") (pintype "passive"))
      (node (ref "RP3") (pin "1") (pinfunction "1_1") (pintype "passive"))
      (node (ref "X3") (pin "6") (pinfunction "6_6") (pintype "passive"))
    )
    (net (code "22") (name "C2M") (class "Default")
      (node (ref "CCM2") (pin "1") (pinfunction "1_1") (pintype "passive"))
      (node (ref "CCM3") (pin "2") (pinfunction "2_2") (pintype "passive"))
      (node (ref "DCM2") (pin "C") (pinfunction "C_C") (pintype "passive"))
      (node (ref "DCM3") (pin "A") (pinfunction "A_A") (pintype "passive"))
      (node (ref "IC2") (pin "22") (pinfunction "C2_22") (pintype "bidirectional"))
      (node (ref "RCM2") (pin "2") (pinfunction "2_2") (pintype "passive"))
    )
    (net (code "23") (name "C3") (class "Default")
      (node (ref "QB3") (pin "2") (pinfunction "S_2") (pintype "passive"))
      (node (ref "RCM3") (pin "1") (pinfunction "1_1") (pintype "passive"))
      (node (ref "RP4") (pin "1") (pinfunction "1_1") (pintype "passive"))
      (node (ref "X6") (pin "2") (pinfunction "1_2") (pintype "passive"))
    )
    (net (code "24") (name "C3M") (class "Default")
      (node (ref "CCM3") (pin "1") (pinfunction "1_1") (pintype "passive"))
      (node (ref "CCM4") (pin "2") (pinfunction "2_2") (pintype "passive"))
      (node (ref "DCM3") (pin "C") (pinfunction "C_C") (pintype "passive"))
      (node (ref "DCM4") (pin "A") (pinfunction "A_A") (pintype "passive"))
      (node (ref "IC2") (pin "20") (pinfunction "C3_20") (pintype "bidirectional"))
      (node (ref "RCM3") (pin "2") (pinfunction "2_2") (pintype "passive"))
    )
    (net (code "25") (name "C4") (class "Default")
      (node (ref "QB4") (pin "2") (pinfunction "S_2") (pintype "passive"))
      (node (ref "RCM4") (pin "1") (pinfunction "1_1") (pintype "passive"))
      (node (ref "RP5") (pin "1") (pinfunction "1_1") (pintype "passive"))
      (node (ref "X3") (pin "5") (pinfunction "5_5") (pintype "passive"))
    )
    (net (code "26") (name "C4M") (class "Default")
      (node (ref "CCM4") (pin "1") (pinfunction "1_1") (pintype "passive"))
      (node (ref "CCM5") (pin "2") (pinfunction "2_2") (pintype "passive"))
      (node (ref "DCM4") (pin "C") (pinfunction "C_C") (pintype "passive"))
      (node (ref "DCM5") (pin "A") (pinfunction "A_A") (pintype "passive"))
      (node (ref "IC2") (pin "18") (pinfunction "C4_18") (pintype "bidirectional"))
      (node (ref "RCM4") (pin "2") (pinfunction "2_2") (pintype "passive"))
    )
    (net (code "27") (name "C5") (class "Default")
      (node (ref "QB5") (pin "2") (pinfunction "S_2") (pintype "passive"))
      (node (ref "RCM5") (pin "1") (pinfunction "1_1") (pintype "passive"))
      (node (ref "RP6") (pin "1") (pinfunction "1_1") (pintype "passive"))
      (node (ref "X6") (pin "3") (pinfunction "3_3") (pintype "passive"))
    )
    (net (code "28") (name "C5M") (class "Default")
      (node (ref "CCM5") (pin "1") (pinfunction "1_1") (pintype "passive"))
      (node (ref "CCM6") (pin "2") (pinfunction "2_2") (pintype "passive"))
      (node (ref "DCM5") (pin "C") (pinfunction "C_C") (pintype "passive"))
      (node (ref "DCM6") (pin "A") (pinfunction "A_A") (pintype "passive"))
      (node (ref "IC2") (pin "16") (pinfunction "C5_16") (pintype "bidirectional"))
      (node (ref "RCM5") (pin "2") (pinfunction "2_2") (pintype "passive"))
    )
    (net (code "29") (name "C6") (class "Default")
      (node (ref "QB6") (pin "2") (pinfunction "S_2") (pintype "passive"))
      (node (ref "RCM6") (pin "1") (pinfunction "1_1") (pintype "passive"))
      (node (ref "RP7") (pin "1") (pinfunction "1_1") (pintype "passive"))
      (node (ref "X3") (pin "4") (pinfunction "4_4") (pintype "passive"))
    )
    (net (code "30") (name "C6M") (class "Default")
      (node (ref "CCM6") (pin "1") (pinfunction "1_1") (pintype "passive"))
      (node (ref "CCM7") (pin "2") (pinfunction "2_2") (pintype "passive"))
      (node (ref "DCM6") (pin "C") (pinfunction "C_C") (pintype "passive"))
      (node (ref "DCM7") (pin "A") (pinfunction "A_A") (pintype "passive"))
      (node (ref "IC2") (pin "14") (pinfunction "C6_14") (pintype "bidirectional"))
      (node (ref "RCM6") (pin "2") (pinfunction "2_2") (pintype "passive"))
    )
    (net (code "31") (name "C7") (class "Default")
      (node (ref "QB7") (pin "2") (pinfunction "S_2") (pintype "passive"))
      (node (ref "RCM7") (pin "1") (pinfunction "1_1") (pintype "passive"))
      (node (ref "RP8") (pin "1") (pinfunction "1_1") (pintype "passive"))
      (node (ref "X6") (pin "4") (pinfunction "4_4") (pintype "passive"))
    )
    (net (code "32") (name "C7M") (class "Default")
      (node (ref "CCM7") (pin "1") (pinfunction "1_1") (pintype "passive"))
      (node (ref "CCM8") (pin "2") (pinfunction "2_2") (pintype "passive"))
      (node (ref "DCM7") (pin "C") (pinfunction "C_C") (pintype "passive"))
      (node (ref "DCM8") (pin "A") (pinfunction "A_A") (pintype "passive"))
      (node (ref "IC2") (pin "12") (pinfunction "C7_12") (pintype "bidirectional"))
      (node (ref "RCM7") (pin "2") (pinfunction "2_2") (pintype "passive"))
    )
    (net (code "33") (name "C8") (class "Default")
      (node (ref "QB8") (pin "2") (pinfunction "S_2") (pintype "passive"))
      (node (ref "RCM8") (pin "1") (pinfunction "1_1") (pintype "passive"))
      (node (ref "RP9") (pin "1") (pinfunction "1_1") (pintype "passive"))
      (node (ref "X3") (pin "3") (pinfunction "3_3") (pintype "passive"))
    )
    (net (code "34") (name "C8M") (class "Default")
      (node (ref "CCM8") (pin "1") (pinfunction "1_1") (pintype "passive"))
      (node (ref "CCM9") (pin "2") (pinfunction "2_2") (pintype "passive"))
      (node (ref "DCM8") (pin "C") (pinfunction "C_C") (pintype "passive"))
      (node (ref "DCM9") (pin "A") (pinfunction "A_A") (pintype "passive"))
      (node (ref "IC2") (pin "10") (pinfunction "C8_10") (pintype "bidirectional"))
      (node (ref "RCM8") (pin "2") (pinfunction "2_2") (pintype "passive"))
    )
    (net (code "35") (name "C9") (class "Default")
      (node (ref "QB9") (pin "2") (pinfunction "S_2") (pintype "passive"))
      (node (ref "RCM9") (pin "1") (pinfunction "1_1") (pintype "passive"))
      (node (ref "RP10") (pin "1") (pinfunction "1_1") (pintype "passive"))
      (node (ref "X6") (pin "5") (pinfunction "5_5") (pintype "passive"))
    )
    (net (code "36") (name "C9M") (class "Default")
      (node (ref "CCM10") (pin "2") (pinfunction "2_2") (pintype "passive"))
      (node (ref "CCM9") (pin "1") (pinfunction "1_1") (pintype "passive"))
      (node (ref "DCM10") (pin "A") (pinfunction "A_A") (pintype "passive"))
      (node (ref "DCM9") (pin "C") (pinfunction "C_C") (pintype "passive"))
      (node (ref "IC2") (pin "8") (pinfunction "C9_8") (pintype "bidirectional"))
      (node (ref "RCM9") (pin "2") (pinfunction "2_2") (pintype "passive"))
    )
    (net (code "37") (name "C10") (class "Default")
      (node (ref "QB10") (pin "2") (pinfunction "S_2") (pintype "passive"))
      (node (ref "RCM10") (pin "1") (pinfunction "1_1") (pintype "passive"))
      (node (ref "RP11") (pin "1") (pinfunction "1_1") (pintype "passive"))
      (node (ref "X3") (pin "2") (pinfunction "1_2") (pintype "passive"))
    )
    (net (code "38") (name "C10M") (class "Default")
      (node (ref "CCM10") (pin "1") (pinfunction "1_1") (pintype "passive"))
      (node (ref "CCM11") (pin "2") (pinfunction "2_2") (pintype "passive"))
      (node (ref "DCM10") (pin "C") (pinfunction "C_C") (pintype "passive"))
      (node (ref "DCM11") (pin "A") (pinfunction "A_A") (pintype "passive"))
      (node (ref "IC2") (pin "6") (pinfunction "C10_6") (pintype "bidirectional"))
      (node (ref "RCM10") (pin "2") (pinfunction "2_2") (pintype "passive"))
    )
    (net (code "39") (name "C11") (class "Default")
      (node (ref "QB11") (pin "2") (pinfunction "S_2") (pintype "passive"))
      (node (ref "RCM11") (pin "1") (pinfunction "1_1") (pintype "passive"))
      (node (ref "RP12") (pin "1") (pinfunction "1_1") (pintype "passive"))
      (node (ref "X6") (pin "6") (pinfunction "6_6") (pintype "passive"))
    )
    (net (code "40") (name "C11M") (class "Default")
      (node (ref "CCM11") (pin "1") (pinfunction "1_1") (pintype "passive"))
      (node (ref "CCM12") (pin "2") (pinfunction "2_2") (pintype "passive"))
      (node (ref "DCM11") (pin "C") (pinfunction "C_C") (pintype "passive"))
      (node (ref "DCM12") (pin "A") (pinfunction "A_A") (pintype "passive"))
      (node (ref "IC2") (pin "4") (pinfunction "C11_4") (pintype "bidirectional"))
      (node (ref "RCM11") (pin "2") (pinfunction "2_2") (pintype "passive"))
    )
    (net (code "41") (name "C12") (class "Default")
      (node (ref "L7") (pin "1") (pinfunction "1_1") (pintype "passive"))
      (node (ref "QB12") (pin "2") (pinfunction "S_2") (pintype "passive"))
      (node (ref "RCM12") (pin "1") (pinfunction "1_1") (pintype "passive"))
      (node (ref "X3") (pin "1") (pinfunction "2_1") (pintype "passive"))
    )
    (net (code "42") (name "C12M") (class "Default")
      (node (ref "CCM12") (pin "1") (pinfunction "1_1") (pintype "passive"))
      (node (ref "DCM12") (pin "C") (pinfunction "C_C") (pintype "passive"))
      (node (ref "IC2") (pin "2") (pinfunction "C12_2") (pintype "bidirectional"))
      (node (ref "RCM12") (pin "2") (pinfunction "2_2") (pintype "passive"))
    )
    (net (code "43") (name "CANH") (class "Default")
      (node (ref "L12") (pin "4") (pinfunction "4_4") (pintype "passive"))
      (node (ref "RV3") (pin "1") (pinfunction "1_1") (pintype "passive"))
      (node (ref "X7") (pin "3") (pinfunction "3_3") (pintype "passive"))
      (node (ref "X7") (pin "7") (pinfunction "7_7") (pintype "passive"))
    )
    (net (code "44") (name "CANL") (class "Default")
      (node (ref "L12") (pin "3") (pinfunction "2_3") (pintype "passive"))
      (node (ref "RV2") (pin "1") (pinfunction "1_1") (pintype "passive"))
      (node (ref "X7") (pin "2") (pinfunction "2_2") (pintype "passive"))
      (node (ref "X7") (pin "6") (pinfunction "6_6") (pintype "passive"))
    )
    (net (code "45") (name "CANRX") (class "Default")
      (node (ref "R7") (pin "2") (pinfunction "2_2") (pintype "passive"))
      (node (ref "U$2") (pin "P$14") (pinfunction "O1_P$14") (pintype "bidirectional"))
    )
    (net (code "46") (name "CANTX") (class "Default")
      (node (ref "R6") (pin "2") (pinfunction "2_2") (pintype "passive"))
      (node (ref "U$2") (pin "P$13") (pinfunction "I2_P$13") (pintype "bidirectional"))
    )
    (net (code "47") (name "CAR+5V") (class "Default")
      (node (ref "C17") (pin "1") (pinfunction "1_1") (pintype "passive"))
      (node (ref "C6") (pin "1") (pinfunction "1_1") (pintype "passive"))
      (node (ref "C7") (pin "1") (pinfunction "1_1") (pintype "passive"))
      (node (ref "IC5") (pin "3") (pinfunction "VDD_3") (pintype "bidirectional"))
      (node (ref "JP1") (pin "1") (pinfunction "1_1") (pintype "passive"))
      (node (ref "REG5_C3") (pin "1") (pinfunction "1_1") (pintype "passive"))
      (node (ref "REG5_C5") (pin "1") (pinfunction "1_1") (pintype "passive"))
      (node (ref "REG5_D1") (pin "A") (pinfunction "A_A") (pintype "passive"))
      (node (ref "REG5_L") (pin "2") (pinfunction "2_2") (pintype "passive"))
      (node (ref "REG5_R2") (pin "2") (pinfunction "2_2") (pintype "passive"))
      (node (ref "U$2") (pin "P$1") (pinfunction "VDD_P$1") (pintype "bidirectional"))
      (node (ref "U$2") (pin "P$6") (pinfunction "RCSEL_P$6") (pintype "bidirectional"))
      (node (ref "U$2") (pin "P$7") (pinfunction "EN1_P$7") (pintype "bidirectional"))
    )
    (net (code "48") (name "CARGND") (class "Default")
      (node (ref "C17") (pin "2") (pinfunction "2_2") (pintype "passive"))
      (node (ref "C6") (pin "2") (pinfunction "2_2") (pintype "passive"))
      (node (ref "C7") (pin "2") (pinfunction "2_2") (pintype "passive"))
      (node (ref "IC3") (pin "2") (pinfunction "GND_2") (pintype "bidirectional"))
      (node (ref "IC5") (pin "2") (pinfunction "VSS_2") (pintype "bidirectional"))
      (node (ref "R39") (pin "2") (pinfunction "2_2") (pintype "passive"))
      (node (ref "REG5_C1") (pin "2") (pinfunction "2_2") (pintype "passive"))
      (node (ref "REG5_C3") (pin "2") (pinfunction "2_2") (pintype "passive"))
      (node (ref "REG5_C4") (pin "2") (pinfunction "2_2") (pintype "passive"))
      (node (ref "REG5_C5") (pin "2") (pinfunction "2_2") (pintype "passive"))
      (node (ref "REG5_D2") (pin "2") (pinfunction "A_2") (pintype "passive"))
      (node (ref "REG5_R1") (pin "1") (pinfunction "1_1") (pintype "passive"))
      (node (ref "RV1") (pin "2") (pinfunction "2_2") (pintype "passive"))
      (node (ref "RV2") (pin "2") (pinfunction "2_2") (pintype "passive"))
      (node (ref "RV3") (pin "2") (pinfunction "2_2") (pintype "passive"))
      (node (ref "U$2") (pin "P$2") (pinfunction "GND_P$2") (pintype "bidirectional"))
      (node (ref "U$2") (pin "P$5") (pinfunction "RCIN_P$5") (pintype "bidirectional"))
      (node (ref "U$2") (pin "P$8") (pinfunction "GND_P$8") (pintype "bidirectional"))
      (node (ref "X7") (pin "4") (pinfunction "4_4") (pintype "passive"))
      (node (ref "X7") (pin "8") (pinfunction "8_8") (pintype "passive"))
    )
    (net (code "49") (name "CARVIN") (class "Default")
      (node (ref "L2") (pin "1") (pinfunction "1_1") (pintype "passive"))
      (node (ref "REG5_C4") (pin "1") (pinfunction "1_1") (pintype "passive"))
      (node (ref "RV1") (pin "1") (pinfunction "1_1") (pintype "passive"))
      (node (ref "X7") (pin "1") (pinfunction "1_1") (pintype "passive"))
      (node (ref "X7") (pin "5") (pinfunction "5_5") (pintype "passive"))
    )
    (net (code "50") (name "CSB") (class "Default")
      (node (ref "IC2") (pin "44") (pinfunction "CSBI_44") (pintype "bidirectional"))
      (node (ref "R1") (pin "2") (pinfunction "2_2") (pintype "passive"))
    )
    (net (code "51") (name "FSM") (class "Default")
      (node (ref "C2") (pin "1") (pinfunction "1_1") (pintype "passive"))
      (node (ref "IC2") (pin "29") (pinfunction "VTEMP1_29") (pintype "bidirectional"))
      (node (ref "R59") (pin "1") (pinfunction "1_1") (pintype "passive"))
      (node (ref "R60") (pin "2") (pinfunction "2_2") (pintype "passive"))
    )
    (net (code "52") (name "GND") (class "Default")
      (node (ref "C1") (pin "2") (pinfunction "2_2") (pintype "passive"))
      (node (ref "C14") (pin "1") (pinfunction "1_1") (pintype "passive"))
      (node (ref "C15") (pin "1") (pinfunction "1_1") (pintype "passive"))
      (node (ref "C2") (pin "2") (pinfunction "2_2") (pintype "passive"))
      (node (ref "C22") (pin "2") (pinfunction "2_2") (pintype "passive"))
      (node (ref "C23") (pin "2") (pinfunction "2_2") (pintype "passive"))
      (node (ref "C27") (pin "2") (pinfunction "2_2") (pintype "passive"))
      (node (ref "C3") (pin "2") (pinfunction "2_2") (pintype "passive"))
      (node (ref "C34") (pin "2") (pinfunction "2_2") (pintype "passive"))
      (node (ref "C5") (pin "2") (pinfunction "2_2") (pintype "passive"))
      (node (ref "CVREF") (pin "1") (pinfunction "1_1") (pintype "passive"))
      (node (ref "CVREG") (pin "1") (pinfunction "1_1") (pintype "passive"))
      (node (ref "DT1") (pin "C") (pinfunction "C_C") (pintype "passive"))
      (node (ref "DT2") (pin "C") (pinfunction "C_C") (pintype "passive"))
      (node (ref "DT3") (pin "C") (pinfunction "C_C") (pintype "passive"))
      (node (ref "DT4") (pin "C") (pinfunction "C_C") (pintype "passive"))
      (node (ref "DT5") (pin "C") (pinfunction "C_C") (pintype "passive"))
      (node (ref "DT6") (pin "C") (pinfunction "C_C") (pintype "passive"))
      (node (ref "IC1") (pin "41") (pinfunction "VSS_41") (pintype "bidirectional"))
      (node (ref "IC1") (pin "5") (pinfunction "VSS_5") (pintype "bidirectional"))
      (node (ref "IC2") (pin "27") (pinfunction "V-_27") (pintype "bidirectional"))
      (node (ref "IC2") (pin "33") (pinfunction "TOS_33") (pintype "bidirectional"))
      (node (ref "IC2") (pin "34") (pinfunction "WDTB_34") (pintype "bidirectional"))
      (node (ref "IC2") (pin "35") (pinfunction "GPIO1_35") (pintype "bidirectional"))
      (node (ref "IC2") (pin "36") (pinfunction "GPIO2_36") (pintype "bidirectional"))
      (node (ref "IC2") (pin "37") (pinfunction "A0_37") (pintype "bidirectional"))
      (node (ref "IC2") (pin "38") (pinfunction "A1_38") (pintype "bidirectional"))
      (node (ref "IC2") (pin "39") (pinfunction "A2_39") (pintype "bidirectional"))
      (node (ref "IC2") (pin "40") (pinfunction "A3_40") (pintype "bidirectional"))
      (node (ref "J1") (pin "6") (pinfunction "6_6") (pintype "passive"))
      (node (ref "NTC_C1") (pin "2") (pinfunction "2_2") (pintype "passive"))
      (node (ref "NTC_C2") (pin "2") (pinfunction "2_2") (pintype "passive"))
      (node (ref "NTC_C3") (pin "2") (pinfunction "2_2") (pintype "passive"))
      (node (ref "NTC_C4") (pin "2") (pinfunction "2_2") (pintype "passive"))
      (node (ref "Q2") (pin "2") (pinfunction "S_2") (pintype "passive"))
      (node (ref "R11") (pin "1") (pinfunction "1_1") (pintype "passive"))
      (node (ref "R60") (pin "1") (pinfunction "1_1") (pintype "passive"))
      (node (ref "RGQ1_3") (pin "1") (pinfunction "1_1") (pintype "passive"))
      (node (ref "U$2") (pin "P$11") (pinfunction "VSEL_P$11") (pintype "bidirectional"))
      (node (ref "U$2") (pin "P$15") (pinfunction "GNDISO_P$15") (pintype "bidirectional"))
      (node (ref "U$2") (pin "P$9") (pinfunction "GNDISO_P$9") (pintype "bidirectional"))
      (node (ref "V-R") (pin "2") (pinfunction "2_2") (pintype "passive"))
      (node (ref "X1") (pin "3") (pinfunction "3_3") (pintype "passive"))
    )
    (net (code "53") (name "ISP_CAN") (class "Default")
      (node (ref "IC1") (pin "14") (pinfunction "PIO0_3_14") (pintype "bidirectional"))
      (node (ref "R11") (pin "2") (pinfunction "2_2") (pintype "passive"))
    )
    (net (code "54") (name "ISP_ENTER") (class "Default")
      (node (ref "IC1") (pin "4") (pinfunction "PIO0_1/CLKOUT/CT32B0_MAT2_4") (pintype "bidirectional"))
      (node (ref "J1") (pin "5") (pinfunction "5_5") (pintype "passive"))
      (node (ref "R15") (pin "2") (pinfunction "2_2") (pintype "passive"))
    )
    (net (code "55") (name "LED1") (class "Default")
      (node (ref "IC1") (pin "24") (pinfunction "PIO2_9_24") (pintype "bidirectional"))
      (node (ref "LED1") (pin "C") (pinfunction "C_C") (pintype "passive"))
    )
    (net (code "56") (name "LED2") (class "Default")
      (node (ref "IC1") (pin "25") (pinfunction "PIO2_10_25") (pintype "bidirectional"))
      (node (ref "LED2") (pin "C") (pinfunction "C_C") (pintype "passive"))
    )
    (net (code "57") (name "MISO0") (class "Default")
      (node (ref "IC1") (pin "27") (pinfunction "PIO0_8/MISO0/CT16B0_MAT0_27") (pintype "bidirectional"))
      (node (ref "R4") (pin "1") (pinfunction "1_1") (pintype "passive"))
    )
    (net (code "58") (name "MISO1") (class "Default")
      (node (ref "IC1") (pin "26") (pinfunction "PIO2_2/~{DCD}/MISO1_26") (pintype "bidirectional"))
    )
    (net (code "59") (name "MOSI0") (class "Default")
      (node (ref "IC1") (pin "28") (pinfunction "PIO0_9/MOSI0/CT16B0_MAT1_28") (pintype "bidirectional"))
      (node (ref "R5") (pin "1") (pinfunction "1_1") (pintype "passive"))
    )
    (net (code "60") (name "MOSI1") (class "Default")
      (node (ref "IC1") (pin "38") (pinfunction "PIO2_3/~{RI}/MOSI1_38") (pintype "bidirectional"))
    )
    (net (code "61") (name "Net-(IC1-CANRX)") (class "Default")
      (node (ref "IC1") (pin "19") (pinfunction "CANRX_19") (pintype "bidirectional"))
      (node (ref "R7") (pin "1") (pinfunction "1_1") (pintype "passive"))
    )
    (net (code "62") (name "Net-(IC1-CANTX)") (class "Default")
      (node (ref "IC1") (pin "20") (pinfunction "CANTX_20") (pintype "bidirectional"))
      (node (ref "R6") (pin "1") (pinfunction "1_1") (pintype "passive"))
    )
    (net (code "63") (name "Net-(IC1-XTALIN)") (class "Default")
      (node (ref "C15") (pin "2") (pinfunction "2_2") (pintype "passive"))
      (node (ref "IC1") (pin "6") (pinfunction "XTALIN_6") (pintype "bidirectional"))
      (node (ref "Y1") (pin "2") (pinfunction "2_2") (pintype "passive"))
    )
    (net (code "64") (name "Net-(IC1-XTALOUT)") (class "Default")
      (node (ref "C14") (pin "2") (pinfunction "2_2") (pintype "passive"))
      (node (ref "IC1") (pin "7") (pinfunction "XTALOUT_7") (pintype "bidirectional"))
      (node (ref "Y1") (pin "1") (pinfunction "1_1") (pintype "passive"))
    )
    (net (code "65") (name "Net-(IC3-BOOST)") (class "Default")
      (node (ref "IC3") (pin "1") (pinfunction "BOOST_1") (pintype "bidirectional"))
      (node (ref "REG5_C2") (pin "1") (pinfunction "1_1") (pintype "passive"))
      (node (ref "REG5_D1") (pin "C") (pinfunction "C_C") (pintype "passive"))
    )
    (net (code "66") (name "Net-(IC3-FB)") (class "Default")
      (node (ref "IC3") (pin "3") (pinfunction "FB_3") (pintype "bidirectional"))
      (node (ref "REG5_R1") (pin "2") (pinfunction "2_2") (pintype "passive"))
      (node (ref "REG5_R2") (pin "1") (pinfunction "1_1") (pintype "passive"))
    )
    (net (code "67") (name "Net-(IC3-SW)") (class "Default")
      (node (ref "IC3") (pin "6") (pinfunction "SW_6") (pintype "bidirectional"))
      (node (ref "REG5_C2") (pin "2") (pinfunction "2_2") (pintype "passive"))
      (node (ref "REG5_D2") (pin "1") (pinfunction "C_1") (pintype "passive"))
      (node (ref "REG5_L") (pin "1") (pinfunction "1_1") (pintype "passive"))
    )
    (net (code "68") (name "Net-(IC3-VIN)") (class "Default")
      (node (ref "IC3") (pin "4") (pinfunction "~{SHDN}_4") (pintype "bidirectional"))
      (node (ref "IC3") (pin "5") (pinfunction "VIN_5") (pintype "bidirectional"))
      (node (ref "L2") (pin "2") (pinfunction "2_2") (pintype "passive"))
      (node (ref "REG5_C1") (pin "1") (pinfunction "1_1") (pintype "passive"))
    )
    (net (code "69") (name "Net-(IC5-CANH)") (class "Default")
      (node (ref "IC5") (pin "7") (pinfunction "CANH_7") (pintype "bidirectional"))
      (node (ref "L12") (pin "1") (pinfunction "3_1") (pintype "passive"))
    )
    (net (code "70") (name "Net-(IC5-CANL)") (class "Default")
      (node (ref "IC5") (pin "6") (pinfunction "CANL_6") (pintype "bidirectional"))
      (node (ref "L12") (pin "2") (pinfunction "1_2") (pintype "passive"))
    )
    (net (code "71") (name "Net-(IC5-RS)") (class "Default")
      (node (ref "IC5") (pin "8") (pinfunction "RS_8") (pintype "bidirectional"))
      (node (ref "R39") (pin "1") (pinfunction "1_1") (pintype "passive"))
    )
    (net (code "72") (name "Net-(IC5-RX)") (class "Default")
      (node (ref "IC5") (pin "4") (pinfunction "RX_4") (pintype "bidirectional"))
      (node (ref "R41") (pin "1") (pinfunction "1_1") (pintype "passive"))
    )
    (net (code "73") (name "Net-(IC5-TX)") (class "Default")
      (node (ref "IC5") (pin "1") (pinfunction "TX_1") (pintype "bidirectional"))
      (node (ref "R40") (pin "1") (pinfunction "1_1") (pintype "passive"))
    )
    (net (code "74") (name "Net-(L7-Pad2)") (class "Default")
      (node (ref "L7") (pin "2") (pinfunction "2_2") (pintype "passive"))
      (node (ref "V+R") (pin "1") (pinfunction "1_1") (pintype "passive"))
    )
    (net (code "75") (name "Net-(LED1-PadA)") (class "Default")
      (node (ref "LED1") (pin "A") (pinfunction "A_A") (pintype "passive"))
      (node (ref "R2") (pin "1") (pinfunction "1_1") (pintype "passive"))
    )
    (net (code "76") (name "Net-(LED2-PadA)") (class "Default")
      (node (ref "LED2") (pin "A") (pinfunction "A_A") (pintype "passive"))
      (node (ref "R8") (pin "1") (pinfunction "1_1") (pintype "passive"))
    )
    (net (code "77") (name "Net-(Q1-G)") (class "Default")
      (node (ref "D2") (pin "A") (pinfunction "A_A") (pintype "passive"))
      (node (ref "Q1") (pin "1") (pinfunction "G_1") (pintype "passive"))
      (node (ref "RGQ1_1") (pin "2") (pinfunction "2_2") (pintype "passive"))
      (node (ref "RGQ1_2") (pin "2") (pinfunction "2_2") (pintype "passive"))
    )
    (net (code "78") (name "Net-(Q1-S)") (class "Default")
      (node (ref "D1") (pin "C") (pinfunction "C_C") (pintype "passive"))
      (node (ref "D2") (pin "C") (pinfunction "C_C") (pintype "passive"))
      (node (ref "Q1") (pin "2") (pinfunction "S_2") (pintype "passive"))
      (node (ref "RGQ1_1") (pin "1") (pinfunction "1_1") (pintype "passive"))
      (node (ref "V+R") (pin "2") (pinfunction "2_2") (pintype "passive"))
    )
    (net (code "79") (name "Net-(Q2-D)") (class "Default")
      (node (ref "Q2") (pin "3") (pinfunction "D_3") (pintype "passive"))
      (node (ref "RGQ1_2") (pin "1") (pinfunction "1_1") (pintype "passive"))
    )
    (net (code "80") (name "Net-(QB1-D)") (class "Default")
      (node (ref "QB1") (pin "3") (pinfunction "D_3") (pintype "passive"))
      (node (ref "RP1") (pin "2") (pinfunction "2_2") (pintype "passive"))
    )
    (net (code "81") (name "Net-(QB1-G)") (class "Default")
      (node (ref "QB1") (pin "1") (pinfunction "G_1") (pintype "passive"))
      (node (ref "RBG1") (pin "1") (pinfunction "1_1") (pintype "passive"))
    )
    (net (code "82") (name "Net-(QB2-D)") (class "Default")
      (node (ref "QB2") (pin "3") (pinfunction "D_3") (pintype "passive"))
      (node (ref "RP2") (pin "2") (pinfunction "2_2") (pintype "passive"))
    )
    (net (code "83") (name "Net-(QB2-G)") (class "Default")
      (node (ref "QB2") (pin "1") (pinfunction "G_1") (pintype "passive"))
      (node (ref "RBG2") (pin "1") (pinfunction "1_1") (pintype "passive"))
    )
    (net (code "84") (name "Net-(QB3-D)") (class "Default")
      (node (ref "QB3") (pin "3") (pinfunction "D_3") (pintype "passive"))
      (node (ref "RP3") (pin "2") (pinfunction "2_2") (pintype "passive"))
    )
    (net (code "85") (name "Net-(QB3-G)") (class "Default")
      (node (ref "QB3") (pin "1") (pinfunction "G_1") (pintype "passive"))
      (node (ref "RBG3") (pin "1") (pinfunction "1_1") (pintype "passive"))
    )
    (net (code "86") (name "Net-(QB4-D)") (class "Default")
      (node (ref "QB4") (pin "3") (pinfunction "D_3") (pintype "passive"))
      (node (ref "RP4") (pin "2") (pinfunction "2_2") (pintype "passive"))
    )
    (net (code "87") (name "Net-(QB4-G)") (class "Default")
      (node (ref "QB4") (pin "1") (pinfunction "G_1") (pintype "passive"))
      (node (ref "RBG4") (pin "1") (pinfunction "1_1") (pintype "passive"))
    )
    (net (code "88") (name "Net-(QB5-D)") (class "Default")
      (node (ref "QB5") (pin "3") (pinfunction "D_3") (pintype "passive"))
      (node (ref "RP5") (pin "2") (pinfunction "2_2") (pintype "passive"))
    )
    (net (code "89") (name "Net-(QB5-G)") (class "Default")
      (node (ref "QB5") (pin "1") (pinfunction "G_1") (pintype "passive"))
      (node (ref "RBG5") (pin "1") (pinfunction "1_1") (pintype "passive"))
    )
    (net (code "90") (name "Net-(QB6-D)") (class "Default")
      (node (ref "QB6") (pin "3") (pinfunction "D_3") (pintype "passive"))
      (node (ref "RP6") (pin "2") (pinfunction "2_2") (pintype "passive"))
    )
    (net (code "91") (name "Net-(QB6-G)") (class "Default")
      (node (ref "QB6") (pin "1") (pinfunction "G_1") (pintype "passive"))
      (node (ref "RBG6") (pin "1") (pinfunction "1_1") (pintype "passive"))
    )
    (net (code "92") (name "Net-(QB7-D)") (class "Default")
      (node (ref "QB7") (pin "3") (pinfunction "D_3") (pintype "passive"))
      (node (ref "RP7") (pin "2") (pinfunction "2_2") (pintype "passive"))
    )
    (net (code "93") (name "Net-(QB7-G)") (class "Default")
      (node (ref "QB7") (pin "1") (pinfunction "G_1") (pintype "passive"))
      (node (ref "RBG7") (pin "1") (pinfunction "1_1") (pintype "passive"))
    )
    (net (code "94") (name "Net-(QB8-D)") (class "Default")
      (node (ref "QB8") (pin "3") (pinfunction "D_3") (pintype "passive"))
      (node (ref "RP8") (pin "2") (pinfunction "2_2") (pintype "passive"))
    )
    (net (code "95") (name "Net-(QB8-G)") (class "Default")
      (node (ref "QB8") (pin "1") (pinfunction "G_1") (pintype "passive"))
      (node (ref "RBG8") (pin "1") (pinfunction "1_1") (pintype "passive"))
    )
    (net (code "96") (name "Net-(QB9-D)") (class "Default")
      (node (ref "QB9") (pin "3") (pinfunction "D_3") (pintype "passive"))
      (node (ref "RP9") (pin "2") (pinfunction "2_2") (pintype "passive"))
    )
    (net (code "97") (name "Net-(QB9-G)") (class "Default")
      (node (ref "QB9") (pin "1") (pinfunction "G_1") (pintype "passive"))
      (node (ref "RBG9") (pin "1") (pinfunction "1_1") (pintype "passive"))
    )
    (net (code "98") (name "Net-(QB10-D)") (class "Default")
      (node (ref "QB10") (pin "3") (pinfunction "D_3") (pintype "passive"))
      (node (ref "RP10") (pin "2") (pinfunction "2_2") (pintype "passive"))
    )
    (net (code "99") (name "Net-(QB10-G)") (class "Default")
      (node (ref "QB10") (pin "1") (pinfunction "G_1") (pintype "passive"))
      (node (ref "RBG10") (pin "1") (pinfunction "1_1") (pintype "passive"))
    )
    (net (code "100") (name "Net-(QB11-D)") (class "Default")
      (node (ref "QB11") (pin "3") (pinfunction "D_3") (pintype "passive"))
      (node (ref "RP11") (pin "2") (pinfunction "2_2") (pintype "passive"))
    )
    (net (code "101") (name "Net-(QB11-G)") (class "Default")
      (node (ref "QB11") (pin "1") (pinfunction "G_1") (pintype "passive"))
      (node (ref "RBG11") (pin "1") (pinfunction "1_1") (pintype "passive"))
    )
    (net (code "102") (name "Net-(QB12-D)") (class "Default")
      (node (ref "QB12") (pin "3") (pinfunction "D_3") (pintype "passive"))
      (node (ref "RP12") (pin "2") (pinfunction "2_2") (pintype "passive"))
    )
    (net (code "103") (name "Net-(QB12-G)") (class "Default")
      (node (ref "QB12") (pin "1") (pinfunction "G_1") (pintype "passive"))
      (node (ref "RBG12") (pin "1") (pinfunction "1_1") (pintype "passive"))
    )
    (net (code "104") (name "Net-(U$2-I1)") (class "Default")
      (node (ref "R41") (pin "2") (pinfunction "2_2") (pintype "passive"))
      (node (ref "U$2") (pin "P$3") (pinfunction "I1_P$3") (pintype "bidirectional"))
    )
    (net (code "105") (name "Net-(U$2-O2)") (class "Default")
      (node (ref "R40") (pin "2") (pinfunction "2_2") (pintype "passive"))
      (node (ref "U$2") (pin "P$4") (pinfunction "O2_P$4") (pintype "bidirectional"))
    )
    (net (code "106") (name "RTEMP") (class "Default")
      (node (ref "C3") (pin "1") (pinfunction "1_1") (pintype "passive"))
      (node (ref "DT1") (pin "A") (pinfunction "A_A") (pintype "passive"))
      (node (ref "DT2") (pin "A") (pinfunction "A_A") (pintype "passive"))
      (node (ref "DT3") (pin "A") (pinfunction "A_A") (pintype "passive"))
      (node (ref "DT4") (pin "A") (pinfunction "A_A") (pintype "passive"))
      (node (ref "DT5") (pin "A") (pinfunction "A_A") (pintype "passive"))
      (node (ref "DT6") (pin "A") (pinfunction "A_A") (pintype "passive"))
      (node (ref "IC1") (pin "33") (pinfunction "PIO1_0/AD1/CT32B1_CAP0_33") (pintype "bidirectional"))
      (node (ref "R9") (pin "1") (pinfunction "1_1") (pintype "passive"))
    )
    (net (code "107") (name "SCK") (class "Default")
      (node (ref "IC2") (pin "41") (pinfunction "SCKI_41") (pintype "bidirectional"))
      (node (ref "R3") (pin "2") (pinfunction "2_2") (pintype "passive"))
    )
    (net (code "108") (name "SCK0") (class "Default")
      (node (ref "IC1") (pin "22") (pinfunction "PIO0_6/SCK0_22") (pintype "bidirectional"))
      (node (ref "R3") (pin "1") (pinfunction "1_1") (pintype "passive"))
    )
    (net (code "109") (name "SCK1") (class "Default")
      (node (ref "IC1") (pin "13") (pinfunction "PIO2_1/~{DSR}/SCK1_13") (pintype "bidirectional"))
    )
    (net (code "110") (name "SDI") (class "Default")
      (node (ref "IC2") (pin "42") (pinfunction "SDI_42") (pintype "bidirectional"))
      (node (ref "R5") (pin "2") (pinfunction "2_2") (pintype "passive"))
    )
    (net (code "111") (name "SDO") (class "Default")
      (node (ref "IC2") (pin "43") (pinfunction "SDO_43") (pintype "bidirectional"))
      (node (ref "R19") (pin "1") (pinfunction "1_1") (pintype "passive"))
      (node (ref "R4") (pin "2") (pinfunction "2_2") (pintype "passive"))
    )
    (net (code "112") (name "SSEL0") (class "Default")
      (node (ref "IC1") (pin "10") (pinfunction "PIO0_2/SSEL/CT16B0_CAP0_10") (pintype "bidirectional"))
      (node (ref "R1") (pin "1") (pinfunction "1_1") (pintype "passive"))
    )
    (net (code "113") (name "SSEL1") (class "Default")
      (node (ref "IC1") (pin "2") (pinfunction "PIO2_0/~{DTR}/SSEL1_2") (pintype "bidirectional"))
    )
    (net (code "114") (name "SWCLK") (class "Default")
      (node (ref "IC1") (pin "29") (pinfunction "PIO0_10/SWCLK/SCK0/CT16B0_MAT2_29") (pintype "bidirectional"))
      (node (ref "J1") (pin "4") (pinfunction "4_4") (pintype "passive"))
    )
    (net (code "115") (name "SWDIO") (class "Default")
      (node (ref "IC1") (pin "39") (pinfunction "PIO1_3/SWDIO/AD4/CT32B1_MAT2_39") (pintype "bidirectional"))
      (node (ref "J1") (pin "3") (pinfunction "3_3") (pintype "passive"))
    )
    (net (code "116") (name "V+") (class "Default")
      (node (ref "C1") (pin "1") (pinfunction "1_1") (pintype "passive"))
      (node (ref "IC2") (pin "1") (pinfunction "V+_1") (pintype "bidirectional"))
      (node (ref "Q1") (pin "3") (pinfunction "D_3") (pintype "passive"))
      (node (ref "R59") (pin "2") (pinfunction "2_2") (pintype "passive"))
    )
    (net (code "117") (name "VREF") (class "Default")
      (node (ref "CVREF") (pin "2") (pinfunction "2_2") (pintype "passive"))
      (node (ref "IC2") (pin "31") (pinfunction "VREF_31") (pintype "bidirectional"))
    )
    (net (code "118") (name "VREG") (class "Default")
      (node (ref "CVREG") (pin "2") (pinfunction "2_2") (pintype "passive"))
      (node (ref "IC2") (pin "32") (pinfunction "VREG_32") (pintype "bidirectional"))
    )
    (net (code "119") (name "WEF1") (class "Default")
      (node (ref "IC1") (pin "32") (pinfunction "PIO0_11/AD0/CT32B0_MAT3_32") (pintype "bidirectional"))
    )
    (net (code "120") (name "unconnected-(IC1-PIO0_4{slash}SCL-Pad15)") (class "Default")
      (node (ref "IC1") (pin "15") (pinfunction "PIO0_4/SCL_15") (pintype "bidirectional"))
    )
    (net (code "121") (name "unconnected-(IC1-PIO0_5{slash}SDA-Pad16)") (class "Default")
      (node (ref "IC1") (pin "16") (pinfunction "PIO0_5/SDA_16") (pintype "bidirectional"))
    )
    (net (code "122") (name "unconnected-(IC1-PIO0_7{slash}~{CTS}-Pad23)") (class "Default")
      (node (ref "IC1") (pin "23") (pinfunction "PIO0_7/~{CTS}_23") (pintype "bidirectional"))
    )
    (net (code "123") (name "unconnected-(IC1-PIO1_5{slash}~{RTS}{slash}CT32B0_CAP0-Pad45)") (class "Default")
      (node (ref "IC1") (pin "45") (pinfunction "PIO1_5/~{RTS}/CT32B0_CAP0_45") (pintype "bidirectional"))
    )
    (net (code "124") (name "unconnected-(IC1-PIO1_6{slash}RXD{slash}CT32B0_MAT0-Pad46)") (class "Default")
      (node (ref "IC1") (pin "46") (pinfunction "PIO1_6/RXD/CT32B0_MAT0_46") (pintype "bidirectional"))
    )
    (net (code "125") (name "unconnected-(IC1-PIO1_7{slash}TXD{slash}CT32B0_MAT1-Pad47)") (class "Default")
      (node (ref "IC1") (pin "47") (pinfunction "PIO1_7/TXD/CT32B0_MAT1_47") (pintype "bidirectional"))
    )
    (net (code "126") (name "unconnected-(IC1-PIO1_8{slash}CT16B1_CAP0-Pad9)") (class "Default")
      (node (ref "IC1") (pin "9") (pinfunction "PIO1_8/CT16B1_CAP0_9") (pintype "bidirectional"))
    )
    (net (code "127") (name "unconnected-(IC1-PIO1_9{slash}CT16B1_MAT0-Pad17)") (class "Default")
      (node (ref "IC1") (pin "17") (pinfunction "PIO1_9/CT16B1_MAT0_17") (pintype "bidirectional"))
    )
    (net (code "128") (name "unconnected-(IC1-PIO1_10{slash}AD6{slash}CT16B1_MAT1-Pad30)") (class "Default")
      (node (ref "IC1") (pin "30") (pinfunction "PIO1_10/AD6/CT16B1_MAT1_30") (pintype "bidirectional"))
    )
    (net (code "129") (name "unconnected-(IC1-PIO2_4-Pad18)") (class "Default")
      (node (ref "IC1") (pin "18") (pinfunction "PIO2_4_18") (pintype "bidirectional"))
    )
    (net (code "130") (name "unconnected-(IC1-PIO2_5-Pad21)") (class "Default")
      (node (ref "IC1") (pin "21") (pinfunction "PIO2_5_21") (pintype "bidirectional"))
    )
    (net (code "131") (name "unconnected-(IC1-PIO2_6-Pad1)") (class "Default")
      (node (ref "IC1") (pin "1") (pinfunction "PIO2_6_1") (pintype "bidirectional"))
    )
    (net (code "132") (name "unconnected-(IC1-PIO2_7-Pad11)") (class "Default")
      (node (ref "IC1") (pin "11") (pinfunction "PIO2_7_11") (pintype "bidirectional"))
    )
    (net (code "133") (name "unconnected-(IC1-PIO2_8-Pad12)") (class "Default")
      (node (ref "IC1") (pin "12") (pinfunction "PIO2_8_12") (pintype "bidirectional"))
    )
    (net (code "134") (name "unconnected-(IC1-PIO2_11{slash}SCK0-Pad31)") (class "Default")
      (node (ref "IC1") (pin "31") (pinfunction "PIO2_11/SCK0_31") (pintype "bidirectional"))
    )
    (net (code "135") (name "unconnected-(IC1-PIO3_0{slash}~{DTR}-Pad36)") (class "Default")
      (node (ref "IC1") (pin "36") (pinfunction "PIO3_0/~{DTR}_36") (pintype "bidirectional"))
    )
    (net (code "136") (name "unconnected-(IC1-PIO3_1{slash}~{DSR}-Pad37)") (class "Default")
      (node (ref "IC1") (pin "37") (pinfunction "PIO3_1/~{DSR}_37") (pintype "bidirectional"))
    )
    (net (code "137") (name "unconnected-(IC1-PIO3_2{slash}~{DCD}-Pad43)") (class "Default")
      (node (ref "IC1") (pin "43") (pinfunction "PIO3_2/~{DCD}_43") (pintype "bidirectional"))
    )
    (net (code "138") (name "unconnected-(IC1-PIO3_3{slash}~{RI}-Pad48)") (class "Default")
      (node (ref "IC1") (pin "48") (pinfunction "PIO3_3/~{RI}_48") (pintype "bidirectional"))
    )
    (net (code "139") (name "unconnected-(IC5-VRF-Pad5)") (class "Default")
      (node (ref "IC5") (pin "5") (pinfunction "VRF_5") (pintype "bidirectional"))
    )
    (net (code "140") (name "~{RESET}") (class "Default")
      (node (ref "C34") (pin "1") (pinfunction "1_1") (pintype "passive"))
      (node (ref "IC1") (pin "3") (pinfunction "PIO0_0/~{RESET}_3") (pintype "bidirectional"))
      (node (ref "J1") (pin "1") (pinfunction "1_1") (pintype "passive"))
      (node (ref "R52") (pin "2") (pinfunction "2_2") (pintype "passive"))
    )
  )
)
